# Send_Medicine_Motor.net
KiCad netlist of a schematic drawn in Altium Designer
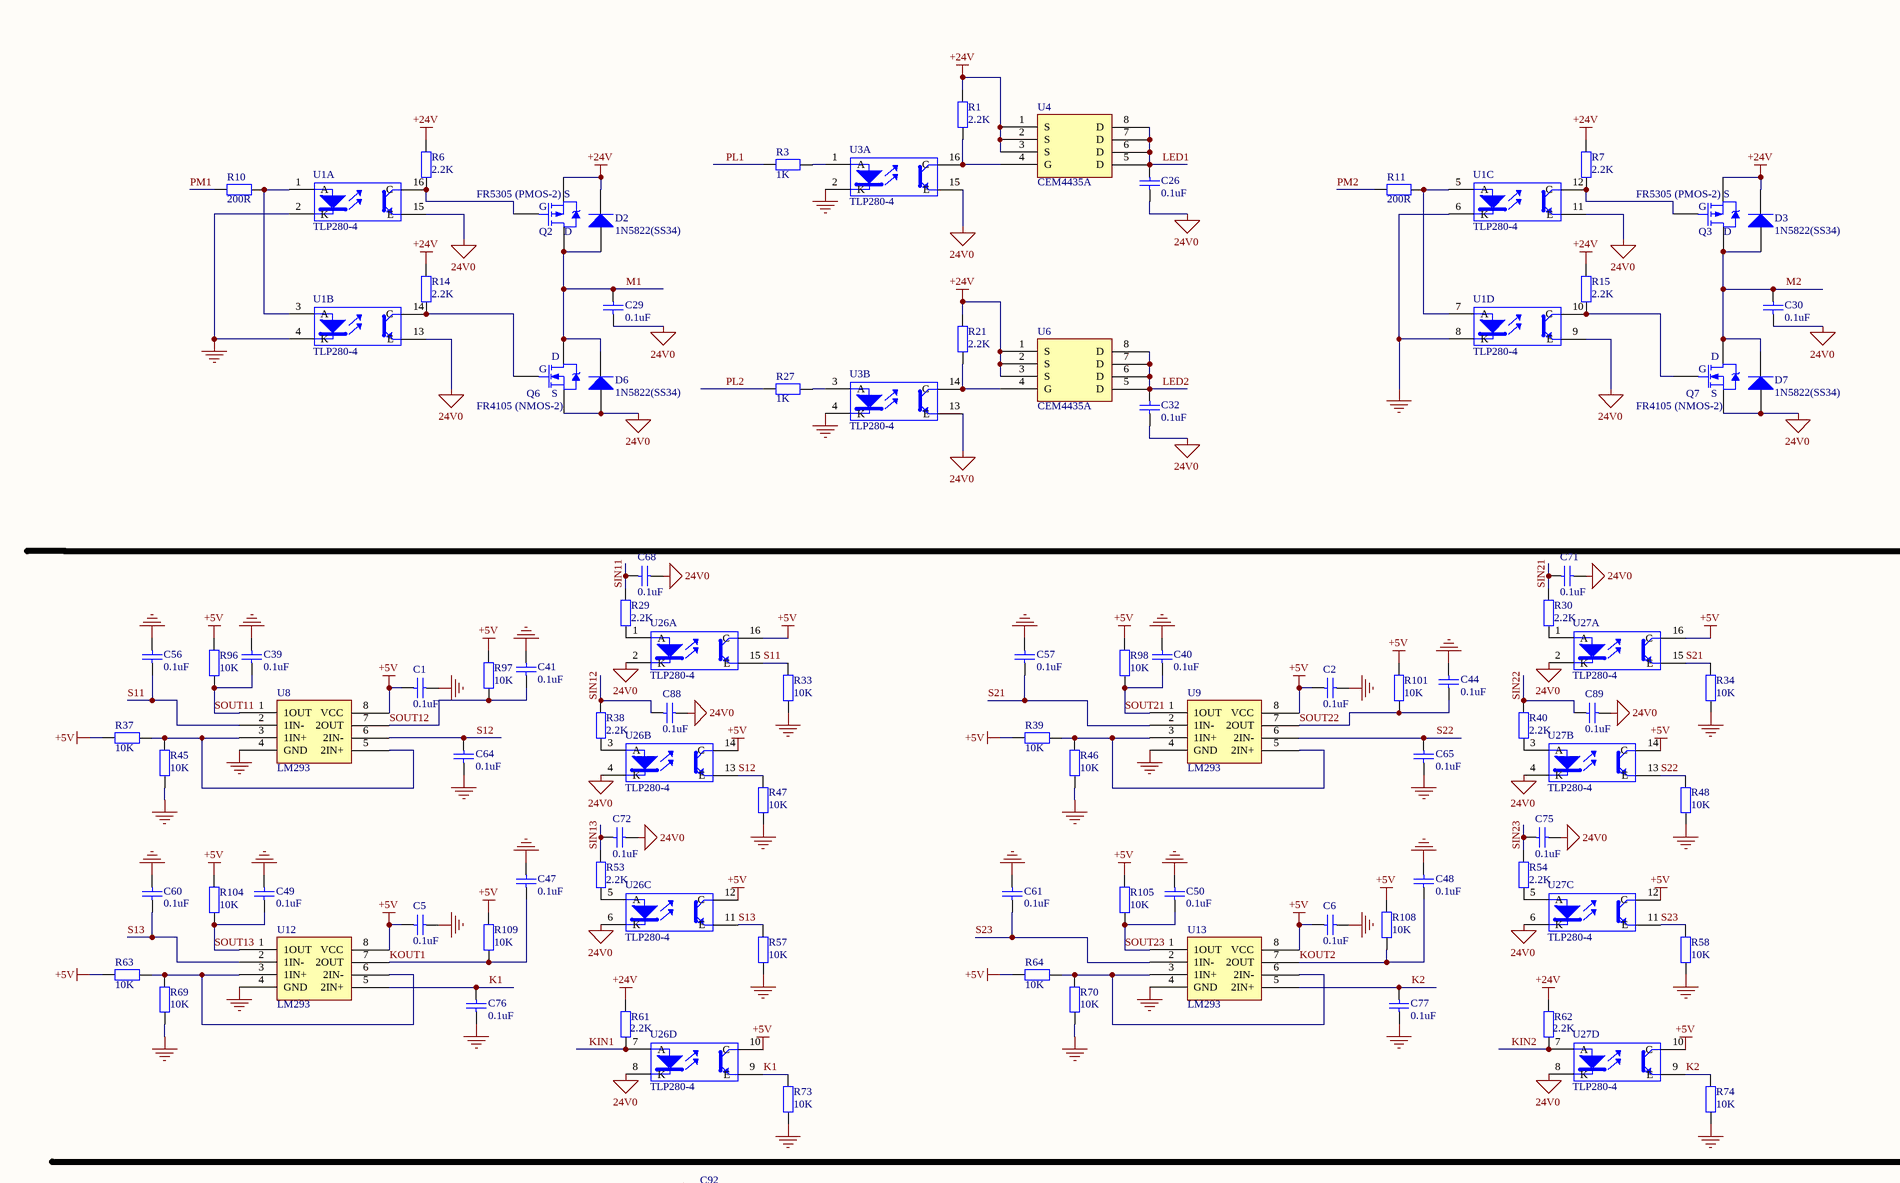
[diagram p0: Send_Medicine_Motor.SchDoc, top left]
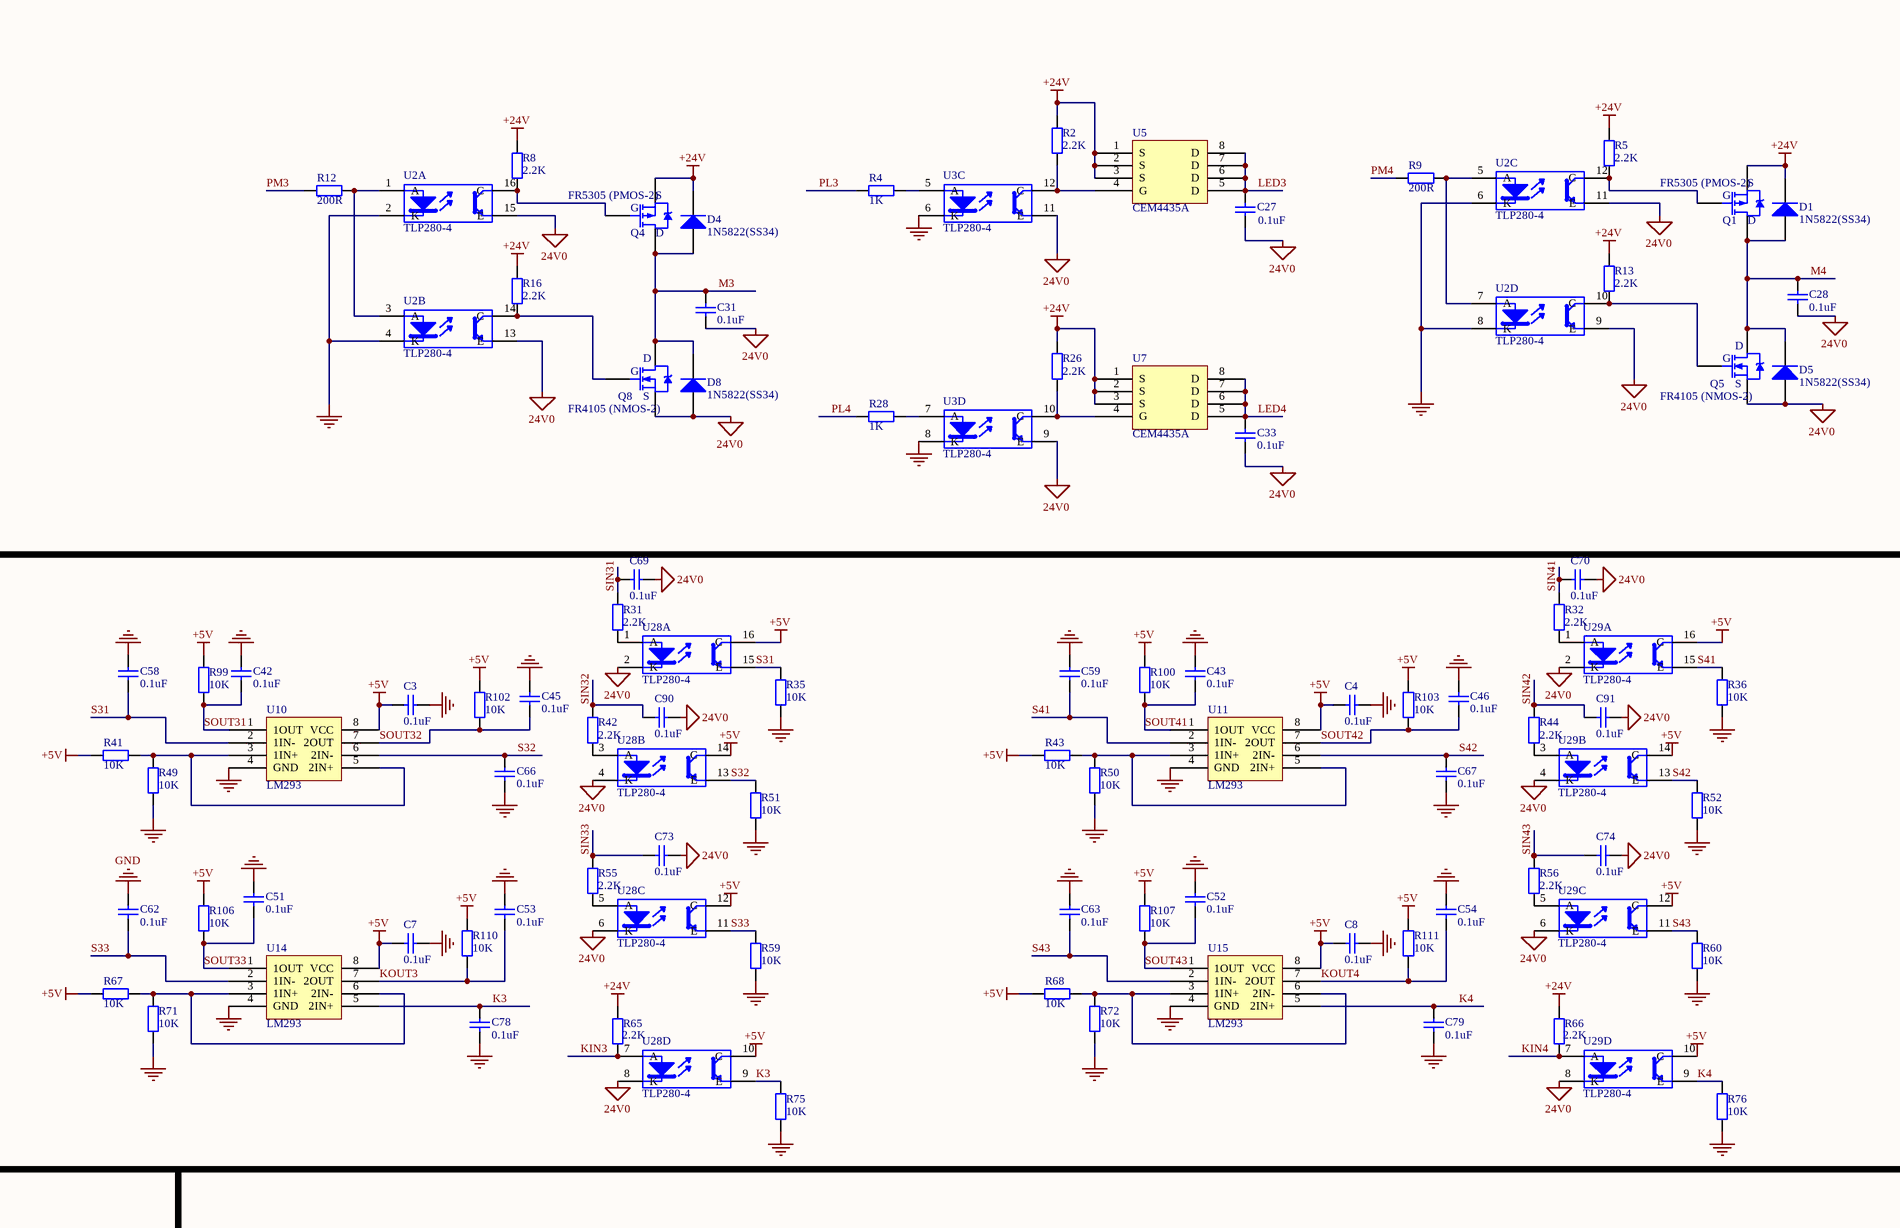
[diagram p1: Send_Medicine_Motor.SchDoc, top middle]
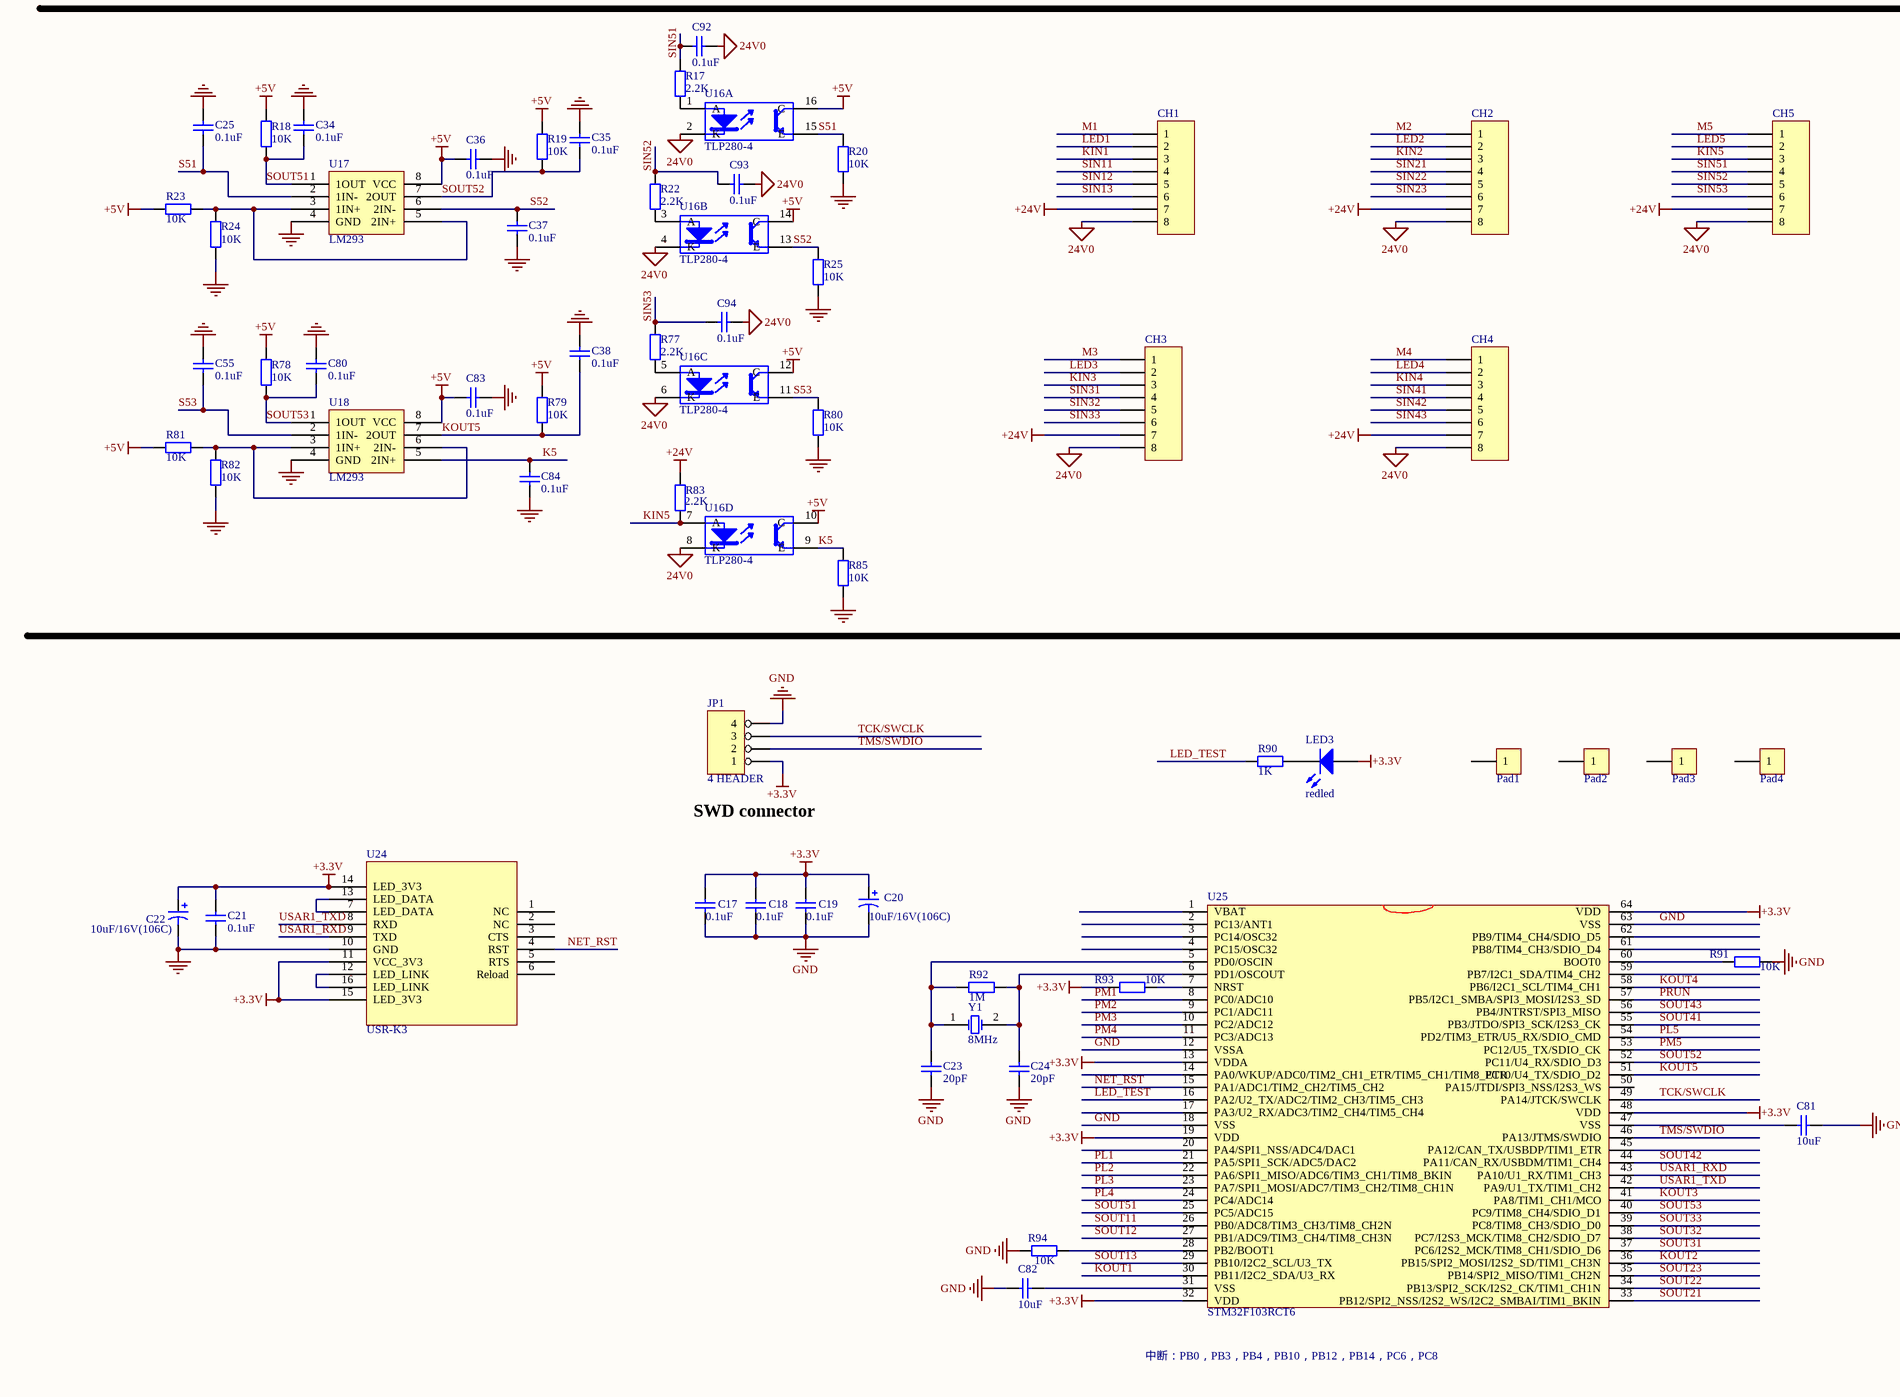
[diagram p2: Send_Medicine_Motor.SchDoc, bottom left]
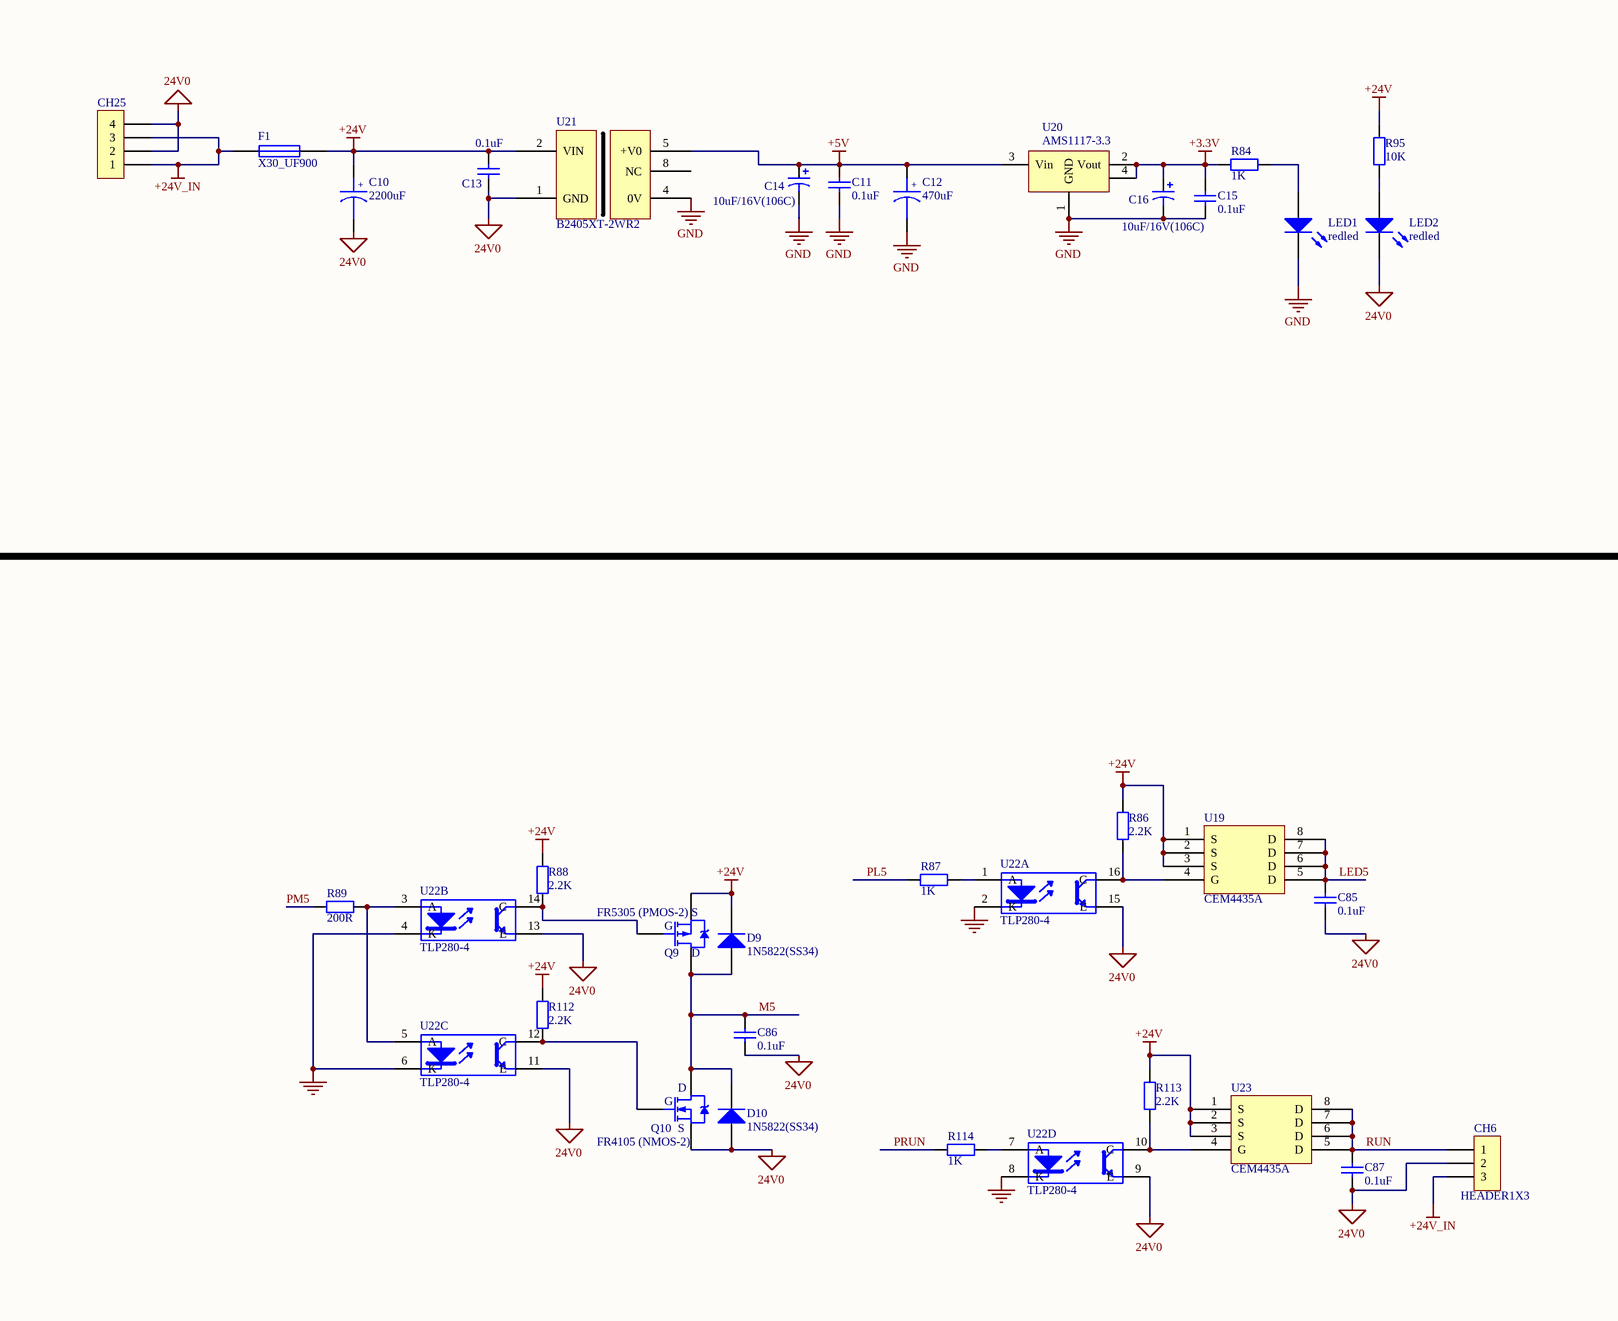
[diagram p3: Send_Medicine_Motor.SchDoc, bottom middle]

(export (version "E")
  (design (tool "Eeschema 10.0.6"))
  (components
    (comp (ref "C1")
      (value "0.1uF")
      (footprint "0805")
      (description "Capacitor")
      (fields (field (name "PUBLISHER") "Altium Limited"))
      (libsource (lib "Miscellaneous Devices") (part "Cap"))
    )
    (comp (ref "C2")
      (value "0.1uF")
      (footprint "0805")
      (description "Capacitor")
      (fields (field (name "PUBLISHER") "Altium Limited"))
      (libsource (lib "Miscellaneous Devices") (part "Cap"))
    )
    (comp (ref "C3")
      (value "0.1uF")
      (footprint "0805")
      (description "Capacitor")
      (fields (field (name "PUBLISHER") "Altium Limited"))
      (libsource (lib "Miscellaneous Devices") (part "Cap"))
    )
    (comp (ref "C4")
      (value "0.1uF")
      (footprint "0805")
      (description "Capacitor")
      (fields (field (name "PUBLISHER") "Altium Limited"))
      (libsource (lib "Miscellaneous Devices") (part "Cap"))
    )
    (comp (ref "C5")
      (value "0.1uF")
      (footprint "0805")
      (description "Capacitor")
      (fields (field (name "PUBLISHER") "Altium Limited"))
      (libsource (lib "Miscellaneous Devices") (part "Cap"))
    )
    (comp (ref "C6")
      (value "0.1uF")
      (footprint "0805")
      (description "Capacitor")
      (fields (field (name "PUBLISHER") "Altium Limited"))
      (libsource (lib "Miscellaneous Devices") (part "Cap"))
    )
    (comp (ref "C7")
      (value "0.1uF")
      (footprint "0805")
      (description "Capacitor")
      (fields (field (name "PUBLISHER") "Altium Limited"))
      (libsource (lib "Miscellaneous Devices") (part "Cap"))
    )
    (comp (ref "C8")
      (value "0.1uF")
      (footprint "0805")
      (description "Capacitor")
      (fields (field (name "PUBLISHER") "Altium Limited"))
      (libsource (lib "Miscellaneous Devices") (part "Cap"))
    )
    (comp (ref "C10")
      (value "2200uF")
      (footprint "C7.8*17")
      (fields (field (name "ALTIUM_UNNAMED_1") "2200uF"))
      (libsource (lib "myIntegrated_Library1") (part "C_2200uF"))
    )
    (comp (ref "C11")
      (value "0.1uF")
      (footprint "0805")
      (description "Capacitor")
      (fields (field (name "PUBLISHER") "Altium Limited"))
      (libsource (lib "Miscellaneous Devices") (part "Cap"))
    )
    (comp (ref "C12")
      (value "470uF")
      (footprint "C5*10")
      (fields (field (name "ALTIUM_UNNAMED_1") "470uF"))
      (libsource (lib "myIntegrated_Library1") (part "C_2200uF"))
    )
    (comp (ref "C13")
      (value "0.1uF")
      (footprint "0805")
      (description "Capacitor")
      (fields (field (name "PUBLISHER") "Altium Limited"))
      (libsource (lib "Miscellaneous Devices") (part "Cap"))
    )
    (comp (ref "C14")
      (value "10uF/16V(106C)")
      (footprint "CAP A-3216")
      (description "Polarized Capacitor (Surface Mount)")
      (fields (field (name "PUBLISHER") "Altium Limited"))
      (libsource (lib "Miscellaneous Devices") (part "Cap Pol3"))
    )
    (comp (ref "C15")
      (value "0.1uF")
      (footprint "0805")
      (description "Capacitor")
      (fields (field (name "PUBLISHER") "Altium Limited"))
      (libsource (lib "Miscellaneous Devices") (part "Cap"))
    )
    (comp (ref "C16")
      (value "10uF/16V(106C)")
      (footprint "CAP A-3216")
      (description "Polarized Capacitor (Surface Mount)")
      (fields (field (name "PUBLISHER") "Altium Limited"))
      (libsource (lib "Miscellaneous Devices") (part "Cap Pol3"))
    )
    (comp (ref "C17")
      (value "0.1uF")
      (footprint "0805")
      (description "Capacitor")
      (fields (field (name "PUBLISHER") "Altium Limited"))
      (libsource (lib "Miscellaneous Devices") (part "Cap"))
    )
    (comp (ref "C18")
      (value "0.1uF")
      (footprint "0805")
      (description "Capacitor")
      (fields (field (name "PUBLISHER") "Altium Limited"))
      (libsource (lib "Miscellaneous Devices") (part "Cap"))
    )
    (comp (ref "C19")
      (value "0.1uF")
      (footprint "0805")
      (description "Capacitor")
      (fields (field (name "PUBLISHER") "Altium Limited"))
      (libsource (lib "Miscellaneous Devices") (part "Cap"))
    )
    (comp (ref "C20")
      (value "10uF/16V(106C)")
      (footprint "CAP A-3216")
      (description "Polarized Capacitor (Surface Mount)")
      (fields (field (name "PUBLISHER") "Altium Limited"))
      (libsource (lib "Miscellaneous Devices") (part "Cap Pol3"))
    )
    (comp (ref "C21")
      (value "0.1uF")
      (footprint "0805")
      (description "Capacitor")
      (fields (field (name "PUBLISHER") "Altium Limited"))
      (libsource (lib "Miscellaneous Devices") (part "Cap"))
    )
    (comp (ref "C22")
      (value "10uF/16V(106C)")
      (footprint "CAP A-3216")
      (description "Polarized Capacitor (Surface Mount)")
      (fields (field (name "PUBLISHER") "Altium Limited"))
      (libsource (lib "Miscellaneous Devices") (part "Cap Pol3"))
    )
    (comp (ref "C23")
      (value "20pF")
      (footprint "0805")
      (description "Capacitor")
      (fields (field (name "PUBLISHER") "Altium Limited"))
      (libsource (lib "开发板元件库") (part "Cap"))
    )
    (comp (ref "C24")
      (value "20pF")
      (footprint "0805")
      (description "Capacitor")
      (fields (field (name "PUBLISHER") "Altium Limited"))
      (libsource (lib "开发板元件库") (part "Cap"))
    )
    (comp (ref "C25")
      (value "0.1uF")
      (footprint "0805")
      (description "Capacitor")
      (fields (field (name "PUBLISHER") "Altium Limited"))
      (libsource (lib "Miscellaneous Devices") (part "Cap"))
    )
    (comp (ref "C26")
      (value "0.1uF")
      (footprint "0805")
      (description "Capacitor")
      (fields (field (name "PUBLISHER") "Altium Limited"))
      (libsource (lib "Miscellaneous Devices") (part "Cap"))
    )
    (comp (ref "C27")
      (value "0.1uF")
      (footprint "0805")
      (description "Capacitor")
      (fields (field (name "PUBLISHER") "Altium Limited"))
      (libsource (lib "Miscellaneous Devices") (part "Cap"))
    )
    (comp (ref "C28")
      (value "0.1uF")
      (footprint "0805")
      (description "Capacitor")
      (fields (field (name "PUBLISHER") "Altium Limited"))
      (libsource (lib "Miscellaneous Devices") (part "Cap"))
    )
    (comp (ref "C29")
      (value "0.1uF")
      (footprint "0805")
      (description "Capacitor")
      (fields (field (name "PUBLISHER") "Altium Limited"))
      (libsource (lib "Miscellaneous Devices") (part "Cap"))
    )
    (comp (ref "C30")
      (value "0.1uF")
      (footprint "0805")
      (description "Capacitor")
      (fields (field (name "PUBLISHER") "Altium Limited"))
      (libsource (lib "Miscellaneous Devices") (part "Cap"))
    )
    (comp (ref "C31")
      (value "0.1uF")
      (footprint "0805")
      (description "Capacitor")
      (fields (field (name "PUBLISHER") "Altium Limited"))
      (libsource (lib "Miscellaneous Devices") (part "Cap"))
    )
    (comp (ref "C32")
      (value "0.1uF")
      (footprint "0805")
      (description "Capacitor")
      (fields (field (name "PUBLISHER") "Altium Limited"))
      (libsource (lib "Miscellaneous Devices") (part "Cap"))
    )
    (comp (ref "C33")
      (value "0.1uF")
      (footprint "0805")
      (description "Capacitor")
      (fields (field (name "PUBLISHER") "Altium Limited"))
      (libsource (lib "Miscellaneous Devices") (part "Cap"))
    )
    (comp (ref "C34")
      (value "0.1uF")
      (footprint "0805")
      (description "Capacitor")
      (fields (field (name "PUBLISHER") "Altium Limited"))
      (libsource (lib "Miscellaneous Devices") (part "Cap"))
    )
    (comp (ref "C35")
      (value "0.1uF")
      (footprint "0805")
      (description "Capacitor")
      (fields (field (name "PUBLISHER") "Altium Limited"))
      (libsource (lib "Miscellaneous Devices") (part "Cap"))
    )
    (comp (ref "C36")
      (value "0.1uF")
      (footprint "0805")
      (description "Capacitor")
      (fields (field (name "PUBLISHER") "Altium Limited"))
      (libsource (lib "Miscellaneous Devices") (part "Cap"))
    )
    (comp (ref "C37")
      (value "0.1uF")
      (footprint "0805")
      (description "Capacitor")
      (fields (field (name "PUBLISHER") "Altium Limited"))
      (libsource (lib "Miscellaneous Devices") (part "Cap"))
    )
    (comp (ref "C38")
      (value "0.1uF")
      (footprint "0805")
      (description "Capacitor")
      (fields (field (name "PUBLISHER") "Altium Limited"))
      (libsource (lib "Miscellaneous Devices") (part "Cap"))
    )
    (comp (ref "C39")
      (value "0.1uF")
      (footprint "0805")
      (description "Capacitor")
      (fields (field (name "PUBLISHER") "Altium Limited"))
      (libsource (lib "Miscellaneous Devices") (part "Cap"))
    )
    (comp (ref "C40")
      (value "0.1uF")
      (footprint "0805")
      (description "Capacitor")
      (fields (field (name "PUBLISHER") "Altium Limited"))
      (libsource (lib "Miscellaneous Devices") (part "Cap"))
    )
    (comp (ref "C41")
      (value "0.1uF")
      (footprint "0805")
      (description "Capacitor")
      (fields (field (name "PUBLISHER") "Altium Limited"))
      (libsource (lib "Miscellaneous Devices") (part "Cap"))
    )
    (comp (ref "C42")
      (value "0.1uF")
      (footprint "0805")
      (description "Capacitor")
      (fields (field (name "PUBLISHER") "Altium Limited"))
      (libsource (lib "Miscellaneous Devices") (part "Cap"))
    )
    (comp (ref "C43")
      (value "0.1uF")
      (footprint "0805")
      (description "Capacitor")
      (fields (field (name "PUBLISHER") "Altium Limited"))
      (libsource (lib "Miscellaneous Devices") (part "Cap"))
    )
    (comp (ref "C44")
      (value "0.1uF")
      (footprint "0805")
      (description "Capacitor")
      (fields (field (name "PUBLISHER") "Altium Limited"))
      (libsource (lib "Miscellaneous Devices") (part "Cap"))
    )
    (comp (ref "C45")
      (value "0.1uF")
      (footprint "0805")
      (description "Capacitor")
      (fields (field (name "PUBLISHER") "Altium Limited"))
      (libsource (lib "Miscellaneous Devices") (part "Cap"))
    )
    (comp (ref "C46")
      (value "0.1uF")
      (footprint "0805")
      (description "Capacitor")
      (fields (field (name "PUBLISHER") "Altium Limited"))
      (libsource (lib "Miscellaneous Devices") (part "Cap"))
    )
    (comp (ref "C47")
      (value "0.1uF")
      (footprint "0805")
      (description "Capacitor")
      (fields (field (name "PUBLISHER") "Altium Limited"))
      (libsource (lib "Miscellaneous Devices") (part "Cap"))
    )
    (comp (ref "C48")
      (value "0.1uF")
      (footprint "0805")
      (description "Capacitor")
      (fields (field (name "PUBLISHER") "Altium Limited"))
      (libsource (lib "Miscellaneous Devices") (part "Cap"))
    )
    (comp (ref "C49")
      (value "0.1uF")
      (footprint "0805")
      (description "Capacitor")
      (fields (field (name "PUBLISHER") "Altium Limited"))
      (libsource (lib "Miscellaneous Devices") (part "Cap"))
    )
    (comp (ref "C50")
      (value "0.1uF")
      (footprint "0805")
      (description "Capacitor")
      (fields (field (name "PUBLISHER") "Altium Limited"))
      (libsource (lib "Miscellaneous Devices") (part "Cap"))
    )
    (comp (ref "C51")
      (value "0.1uF")
      (footprint "0805")
      (description "Capacitor")
      (fields (field (name "PUBLISHER") "Altium Limited"))
      (libsource (lib "Miscellaneous Devices") (part "Cap"))
    )
    (comp (ref "C52")
      (value "0.1uF")
      (footprint "0805")
      (description "Capacitor")
      (fields (field (name "PUBLISHER") "Altium Limited"))
      (libsource (lib "Miscellaneous Devices") (part "Cap"))
    )
    (comp (ref "C53")
      (value "0.1uF")
      (footprint "0805")
      (description "Capacitor")
      (fields (field (name "PUBLISHER") "Altium Limited"))
      (libsource (lib "Miscellaneous Devices") (part "Cap"))
    )
    (comp (ref "C54")
      (value "0.1uF")
      (footprint "0805")
      (description "Capacitor")
      (fields (field (name "PUBLISHER") "Altium Limited"))
      (libsource (lib "Miscellaneous Devices") (part "Cap"))
    )
    (comp (ref "C55")
      (value "0.1uF")
      (footprint "0805")
      (description "Capacitor")
      (fields (field (name "PUBLISHER") "Altium Limited"))
      (libsource (lib "Miscellaneous Devices") (part "Cap"))
    )
    (comp (ref "C56")
      (value "0.1uF")
      (footprint "0805")
      (description "Capacitor")
      (fields (field (name "PUBLISHER") "Altium Limited"))
      (libsource (lib "Miscellaneous Devices") (part "Cap"))
    )
    (comp (ref "C57")
      (value "0.1uF")
      (footprint "0805")
      (description "Capacitor")
      (fields (field (name "PUBLISHER") "Altium Limited"))
      (libsource (lib "Miscellaneous Devices") (part "Cap"))
    )
    (comp (ref "C58")
      (value "0.1uF")
      (footprint "0805")
      (description "Capacitor")
      (fields (field (name "PUBLISHER") "Altium Limited"))
      (libsource (lib "Miscellaneous Devices") (part "Cap"))
    )
    (comp (ref "C59")
      (value "0.1uF")
      (footprint "0805")
      (description "Capacitor")
      (fields (field (name "PUBLISHER") "Altium Limited"))
      (libsource (lib "Miscellaneous Devices") (part "Cap"))
    )
    (comp (ref "C60")
      (value "0.1uF")
      (footprint "0805")
      (description "Capacitor")
      (fields (field (name "PUBLISHER") "Altium Limited"))
      (libsource (lib "Miscellaneous Devices") (part "Cap"))
    )
    (comp (ref "C61")
      (value "0.1uF")
      (footprint "0805")
      (description "Capacitor")
      (fields (field (name "PUBLISHER") "Altium Limited"))
      (libsource (lib "Miscellaneous Devices") (part "Cap"))
    )
    (comp (ref "C62")
      (value "0.1uF")
      (footprint "0805")
      (description "Capacitor")
      (fields (field (name "PUBLISHER") "Altium Limited"))
      (libsource (lib "Miscellaneous Devices") (part "Cap"))
    )
    (comp (ref "C63")
      (value "0.1uF")
      (footprint "0805")
      (description "Capacitor")
      (fields (field (name "PUBLISHER") "Altium Limited"))
      (libsource (lib "Miscellaneous Devices") (part "Cap"))
    )
    (comp (ref "C64")
      (value "0.1uF")
      (footprint "0805")
      (description "Capacitor")
      (fields (field (name "PUBLISHER") "Altium Limited"))
      (libsource (lib "Miscellaneous Devices") (part "Cap"))
    )
    (comp (ref "C65")
      (value "0.1uF")
      (footprint "0805")
      (description "Capacitor")
      (fields (field (name "PUBLISHER") "Altium Limited"))
      (libsource (lib "Miscellaneous Devices") (part "Cap"))
    )
    (comp (ref "C66")
      (value "0.1uF")
      (footprint "0805")
      (description "Capacitor")
      (fields (field (name "PUBLISHER") "Altium Limited"))
      (libsource (lib "Miscellaneous Devices") (part "Cap"))
    )
    (comp (ref "C67")
      (value "0.1uF")
      (footprint "0805")
      (description "Capacitor")
      (fields (field (name "PUBLISHER") "Altium Limited"))
      (libsource (lib "Miscellaneous Devices") (part "Cap"))
    )
    (comp (ref "C68")
      (value "0.1uF")
      (footprint "0805")
      (description "Capacitor")
      (fields (field (name "PUBLISHER") "Altium Limited"))
      (libsource (lib "Miscellaneous Devices") (part "Cap"))
    )
    (comp (ref "C69")
      (value "0.1uF")
      (footprint "0805")
      (description "Capacitor")
      (fields (field (name "PUBLISHER") "Altium Limited"))
      (libsource (lib "Miscellaneous Devices") (part "Cap"))
    )
    (comp (ref "C70")
      (value "0.1uF")
      (footprint "0805")
      (description "Capacitor")
      (fields (field (name "PUBLISHER") "Altium Limited"))
      (libsource (lib "Miscellaneous Devices") (part "Cap"))
    )
    (comp (ref "C71")
      (value "0.1uF")
      (footprint "0805")
      (description "Capacitor")
      (fields (field (name "PUBLISHER") "Altium Limited"))
      (libsource (lib "Miscellaneous Devices") (part "Cap"))
    )
    (comp (ref "C72")
      (value "0.1uF")
      (footprint "0805")
      (description "Capacitor")
      (fields (field (name "PUBLISHER") "Altium Limited"))
      (libsource (lib "Miscellaneous Devices") (part "Cap"))
    )
    (comp (ref "C73")
      (value "0.1uF")
      (footprint "0805")
      (description "Capacitor")
      (fields (field (name "PUBLISHER") "Altium Limited"))
      (libsource (lib "Miscellaneous Devices") (part "Cap"))
    )
    (comp (ref "C74")
      (value "0.1uF")
      (footprint "0805")
      (description "Capacitor")
      (fields (field (name "PUBLISHER") "Altium Limited"))
      (libsource (lib "Miscellaneous Devices") (part "Cap"))
    )
    (comp (ref "C75")
      (value "0.1uF")
      (footprint "0805")
      (description "Capacitor")
      (fields (field (name "PUBLISHER") "Altium Limited"))
      (libsource (lib "Miscellaneous Devices") (part "Cap"))
    )
    (comp (ref "C76")
      (value "0.1uF")
      (footprint "0805")
      (description "Capacitor")
      (fields (field (name "PUBLISHER") "Altium Limited"))
      (libsource (lib "Miscellaneous Devices") (part "Cap"))
    )
    (comp (ref "C77")
      (value "0.1uF")
      (footprint "0805")
      (description "Capacitor")
      (fields (field (name "PUBLISHER") "Altium Limited"))
      (libsource (lib "Miscellaneous Devices") (part "Cap"))
    )
    (comp (ref "C78")
      (value "0.1uF")
      (footprint "0805")
      (description "Capacitor")
      (fields (field (name "PUBLISHER") "Altium Limited"))
      (libsource (lib "Miscellaneous Devices") (part "Cap"))
    )
    (comp (ref "C79")
      (value "0.1uF")
      (footprint "0805")
      (description "Capacitor")
      (fields (field (name "PUBLISHER") "Altium Limited"))
      (libsource (lib "Miscellaneous Devices") (part "Cap"))
    )
    (comp (ref "C80")
      (value "0.1uF")
      (footprint "0805")
      (description "Capacitor")
      (fields (field (name "PUBLISHER") "Altium Limited"))
      (libsource (lib "Miscellaneous Devices") (part "Cap"))
    )
    (comp (ref "C81")
      (value "10uF")
      (footprint "0805")
      (description "Capacitor")
      (fields (field (name "PUBLISHER") "Altium Limited"))
      (libsource (lib "Miscellaneous Devices") (part "Cap"))
    )
    (comp (ref "C82")
      (value "10uF")
      (footprint "0805")
      (description "Capacitor")
      (fields (field (name "PUBLISHER") "Altium Limited"))
      (libsource (lib "Miscellaneous Devices") (part "Cap"))
    )
    (comp (ref "C83")
      (value "0.1uF")
      (footprint "0805")
      (description "Capacitor")
      (fields (field (name "PUBLISHER") "Altium Limited"))
      (libsource (lib "Miscellaneous Devices") (part "Cap"))
    )
    (comp (ref "C84")
      (value "0.1uF")
      (footprint "0805")
      (description "Capacitor")
      (fields (field (name "PUBLISHER") "Altium Limited"))
      (libsource (lib "Miscellaneous Devices") (part "Cap"))
    )
    (comp (ref "C85")
      (value "0.1uF")
      (footprint "0805")
      (description "Capacitor")
      (fields (field (name "PUBLISHER") "Altium Limited"))
      (libsource (lib "Miscellaneous Devices") (part "Cap"))
    )
    (comp (ref "C86")
      (value "0.1uF")
      (footprint "0805")
      (description "Capacitor")
      (fields (field (name "PUBLISHER") "Altium Limited"))
      (libsource (lib "Miscellaneous Devices") (part "Cap"))
    )
    (comp (ref "C87")
      (value "0.1uF")
      (footprint "0805")
      (description "Capacitor")
      (fields (field (name "PUBLISHER") "Altium Limited"))
      (libsource (lib "Miscellaneous Devices") (part "Cap"))
    )
    (comp (ref "C88")
      (value "0.1uF")
      (footprint "0805")
      (description "Capacitor")
      (fields (field (name "PUBLISHER") "Altium Limited"))
      (libsource (lib "Miscellaneous Devices") (part "Cap"))
    )
    (comp (ref "C89")
      (value "0.1uF")
      (footprint "0805")
      (description "Capacitor")
      (fields (field (name "PUBLISHER") "Altium Limited"))
      (libsource (lib "Miscellaneous Devices") (part "Cap"))
    )
    (comp (ref "C90")
      (value "0.1uF")
      (footprint "0805")
      (description "Capacitor")
      (fields (field (name "PUBLISHER") "Altium Limited"))
      (libsource (lib "Miscellaneous Devices") (part "Cap"))
    )
    (comp (ref "C91")
      (value "0.1uF")
      (footprint "0805")
      (description "Capacitor")
      (fields (field (name "PUBLISHER") "Altium Limited"))
      (libsource (lib "Miscellaneous Devices") (part "Cap"))
    )
    (comp (ref "C92")
      (value "0.1uF")
      (footprint "0805")
      (description "Capacitor")
      (fields (field (name "PUBLISHER") "Altium Limited"))
      (libsource (lib "Miscellaneous Devices") (part "Cap"))
    )
    (comp (ref "C93")
      (value "0.1uF")
      (footprint "0805")
      (description "Capacitor")
      (fields (field (name "PUBLISHER") "Altium Limited"))
      (libsource (lib "Miscellaneous Devices") (part "Cap"))
    )
    (comp (ref "C94")
      (value "0.1uF")
      (footprint "0805")
      (description "Capacitor")
      (fields (field (name "PUBLISHER") "Altium Limited"))
      (libsource (lib "Miscellaneous Devices") (part "Cap"))
    )
    (comp (ref "CH1")
      (value "HEADER1X8")
      (footprint "CH3.96-8PIN")
      (description "Header, 8-Pin")
      (libsource (lib "myIntegrated_Library1") (part "HEADER1X8"))
    )
    (comp (ref "CH2")
      (value "HEADER1X8")
      (footprint "CH3.96-8PIN")
      (description "Header, 8-Pin")
      (libsource (lib "myIntegrated_Library1") (part "HEADER1X8"))
    )
    (comp (ref "CH3")
      (value "HEADER1X8")
      (footprint "CH3.96-8PIN")
      (description "Header, 8-Pin")
      (libsource (lib "myIntegrated_Library1") (part "HEADER1X8"))
    )
    (comp (ref "CH4")
      (value "HEADER1X8")
      (footprint "CH3.96-8PIN")
      (description "Header, 8-Pin")
      (libsource (lib "myIntegrated_Library1") (part "HEADER1X8"))
    )
    (comp (ref "CH5")
      (value "HEADER1X8")
      (footprint "CH3.96-8PIN")
      (description "Header, 8-Pin")
      (libsource (lib "myIntegrated_Library1") (part "HEADER1X8"))
    )
    (comp (ref "CH6")
      (value "HEADER1X3")
      (footprint "CH3.96-3PIN")
      (libsource (lib "myIntegrated_Library1") (part "HEADER1X3"))
    )
    (comp (ref "CH25")
      (value "HEADER1X4")
      (footprint "CH3.96-4PIN")
      (libsource (lib "myIntegrated_Library1") (part "HEADER1X4"))
    )
    (comp (ref "D1")
      (value "1N5822(SS34)")
      (description "High Conductance Fast Diode")
      (fields (field (name "PUBLISHER") "Altium Limited"))
      (libsource (lib "Miscellaneous Devices") (part "Diode 1N4148"))
    )
    (comp (ref "D2")
      (value "1N5822(SS34)")
      (description "High Conductance Fast Diode")
      (fields (field (name "PUBLISHER") "Altium Limited"))
      (libsource (lib "Miscellaneous Devices") (part "Diode 1N4148"))
    )
    (comp (ref "D3")
      (value "1N5822(SS34)")
      (description "High Conductance Fast Diode")
      (fields (field (name "PUBLISHER") "Altium Limited"))
      (libsource (lib "Miscellaneous Devices") (part "Diode 1N4148"))
    )
    (comp (ref "D4")
      (value "1N5822(SS34)")
      (description "High Conductance Fast Diode")
      (fields (field (name "PUBLISHER") "Altium Limited"))
      (libsource (lib "Miscellaneous Devices") (part "Diode 1N4148"))
    )
    (comp (ref "D5")
      (value "1N5822(SS34)")
      (description "High Conductance Fast Diode")
      (fields (field (name "PUBLISHER") "Altium Limited"))
      (libsource (lib "Miscellaneous Devices") (part "Diode 1N4148"))
    )
    (comp (ref "D6")
      (value "1N5822(SS34)")
      (description "High Conductance Fast Diode")
      (fields (field (name "PUBLISHER") "Altium Limited"))
      (libsource (lib "Miscellaneous Devices") (part "Diode 1N4148"))
    )
    (comp (ref "D7")
      (value "1N5822(SS34)")
      (description "High Conductance Fast Diode")
      (fields (field (name "PUBLISHER") "Altium Limited"))
      (libsource (lib "Miscellaneous Devices") (part "Diode 1N4148"))
    )
    (comp (ref "D8")
      (value "1N5822(SS34)")
      (description "High Conductance Fast Diode")
      (fields (field (name "PUBLISHER") "Altium Limited"))
      (libsource (lib "Miscellaneous Devices") (part "Diode 1N4148"))
    )
    (comp (ref "D9")
      (value "1N5822(SS34)")
      (description "High Conductance Fast Diode")
      (fields (field (name "PUBLISHER") "Altium Limited"))
      (libsource (lib "Miscellaneous Devices") (part "Diode 1N4148"))
    )
    (comp (ref "D10")
      (value "1N5822(SS34)")
      (description "High Conductance Fast Diode")
      (fields (field (name "PUBLISHER") "Altium Limited"))
      (libsource (lib "Miscellaneous Devices") (part "Diode 1N4148"))
    )
    (comp (ref "F1")
      (value "X30_UF900")
      (footprint "X30UF900")
      (description "Fuse")
      (fields (field (name "PUBLISHER") "Altium Limited"))
      (libsource (lib "Miscellaneous Devices") (part "Fuse 1"))
    )
    (comp (ref "JP1")
      (value "4 HEADER")
      (footprint "CON4_1.5")
      (description "4 Pin Header")
      (libsource (lib "Miscellaneous Devices") (part "4 HEADER"))
    )
    (comp (ref "LED1")
      (value "redled")
      (footprint "LED-0805")
      (description "Typical RED, GREEN, YELLOW, AMBER GaAs LED")
      (fields (field (name "PUBLISHER") "Altium Limited"))
      (libsource (lib "Miscellaneous Devices") (part "LED2"))
    )
    (comp (ref "LED2")
      (value "redled")
      (footprint "LED-0805")
      (description "Typical RED, GREEN, YELLOW, AMBER GaAs LED")
      (fields (field (name "PUBLISHER") "Altium Limited"))
      (libsource (lib "Miscellaneous Devices") (part "LED2"))
    )
    (comp (ref "LED3")
      (value "redled")
      (footprint "LED-0805")
      (description "Typical RED, GREEN, YELLOW, AMBER GaAs LED")
      (fields (field (name "PUBLISHER") "Altium Limited"))
      (libsource (lib "Miscellaneous Devices") (part "LED2"))
    )
    (comp (ref "Pad1")
      (value "Pad")
      (footprint "pad35")
      (libsource (lib "myIntegrated_Library1") (part "Pad"))
    )
    (comp (ref "Pad2")
      (value "Pad")
      (footprint "pad35")
      (libsource (lib "myIntegrated_Library1") (part "Pad"))
    )
    (comp (ref "Pad3")
      (value "Pad")
      (footprint "pad35")
      (libsource (lib "myIntegrated_Library1") (part "Pad"))
    )
    (comp (ref "Pad4")
      (value "Pad")
      (footprint "pad35")
      (libsource (lib "myIntegrated_Library1") (part "Pad"))
    )
    (comp (ref "Q1")
      (value "FR5305 (PMOS-2)")
      (footprint "TO-252")
      (description "P-Channel Power MOSFET")
      (fields (field (name "PUBLISHER") "Altium Limited"))
      (libsource (lib "Miscellaneous Devices") (part "PMOS-2"))
    )
    (comp (ref "Q2")
      (value "FR5305 (PMOS-2)")
      (footprint "TO-252")
      (description "P-Channel Power MOSFET")
      (fields (field (name "PUBLISHER") "Altium Limited"))
      (libsource (lib "Miscellaneous Devices") (part "PMOS-2"))
    )
    (comp (ref "Q3")
      (value "FR5305 (PMOS-2)")
      (footprint "TO-252")
      (description "P-Channel Power MOSFET")
      (fields (field (name "PUBLISHER") "Altium Limited"))
      (libsource (lib "Miscellaneous Devices") (part "PMOS-2"))
    )
    (comp (ref "Q4")
      (value "FR5305 (PMOS-2)")
      (footprint "TO-252")
      (description "P-Channel Power MOSFET")
      (fields (field (name "PUBLISHER") "Altium Limited"))
      (libsource (lib "Miscellaneous Devices") (part "PMOS-2"))
    )
    (comp (ref "Q5")
      (value "FR4105 (NMOS-2)")
      (footprint "TO-252")
      (description "N-Channel Power MOSFET")
      (fields (field (name "PUBLISHER") "Altium Limited"))
      (libsource (lib "Miscellaneous Devices") (part "NMOS-2"))
    )
    (comp (ref "Q6")
      (value "FR4105 (NMOS-2)")
      (footprint "TO-252")
      (description "N-Channel Power MOSFET")
      (fields (field (name "PUBLISHER") "Altium Limited"))
      (libsource (lib "Miscellaneous Devices") (part "NMOS-2"))
    )
    (comp (ref "Q7")
      (value "FR4105 (NMOS-2)")
      (footprint "TO-252")
      (description "N-Channel Power MOSFET")
      (fields (field (name "PUBLISHER") "Altium Limited"))
      (libsource (lib "Miscellaneous Devices") (part "NMOS-2"))
    )
    (comp (ref "Q8")
      (value "FR4105 (NMOS-2)")
      (footprint "TO-252")
      (description "N-Channel Power MOSFET")
      (fields (field (name "PUBLISHER") "Altium Limited"))
      (libsource (lib "Miscellaneous Devices") (part "NMOS-2"))
    )
    (comp (ref "Q9")
      (value "FR5305 (PMOS-2)")
      (footprint "TO-252")
      (description "P-Channel Power MOSFET")
      (fields (field (name "PUBLISHER") "Altium Limited"))
      (libsource (lib "Miscellaneous Devices") (part "PMOS-2"))
    )
    (comp (ref "Q10")
      (value "FR4105 (NMOS-2)")
      (footprint "TO-252")
      (description "N-Channel Power MOSFET")
      (fields (field (name "PUBLISHER") "Altium Limited"))
      (libsource (lib "Miscellaneous Devices") (part "NMOS-2"))
    )
    (comp (ref "R1")
      (value "2.2K")
      (footprint "0805")
      (description "Resistor")
      (fields (field (name "PUBLISHER") "Altium Limited"))
      (libsource (lib "") (part "Res2_1"))
    )
    (comp (ref "R2")
      (value "2.2K")
      (footprint "0805")
      (description "Resistor")
      (fields (field (name "PUBLISHER") "Altium Limited"))
      (libsource (lib "") (part "Res2_1"))
    )
    (comp (ref "R3")
      (value "1K")
      (footprint "0805")
      (description "Resistor")
      (fields (field (name "PUBLISHER") "Altium Limited"))
      (libsource (lib "") (part "Res2_2"))
    )
    (comp (ref "R4")
      (value "1K")
      (footprint "0805")
      (description "Resistor")
      (fields (field (name "PUBLISHER") "Altium Limited"))
      (libsource (lib "") (part "Res2_2"))
    )
    (comp (ref "R5")
      (value "2.2K")
      (footprint "0805")
      (description "Resistor")
      (fields (field (name "PUBLISHER") "Altium Limited"))
      (libsource (lib "") (part "Res2_1"))
    )
    (comp (ref "R6")
      (value "2.2K")
      (footprint "0805")
      (description "Resistor")
      (fields (field (name "PUBLISHER") "Altium Limited"))
      (libsource (lib "") (part "Res2_1"))
    )
    (comp (ref "R7")
      (value "2.2K")
      (footprint "0805")
      (description "Resistor")
      (fields (field (name "PUBLISHER") "Altium Limited"))
      (libsource (lib "") (part "Res2_1"))
    )
    (comp (ref "R8")
      (value "2.2K")
      (footprint "0805")
      (description "Resistor")
      (fields (field (name "PUBLISHER") "Altium Limited"))
      (libsource (lib "") (part "Res2_1"))
    )
    (comp (ref "R9")
      (value "200R")
      (footprint "0805")
      (description "Resistor")
      (fields (field (name "PUBLISHER") "Altium Limited"))
      (libsource (lib "") (part "Res2_2"))
    )
    (comp (ref "R10")
      (value "200R")
      (footprint "0805")
      (description "Resistor")
      (fields (field (name "PUBLISHER") "Altium Limited"))
      (libsource (lib "") (part "Res2_2"))
    )
    (comp (ref "R11")
      (value "200R")
      (footprint "0805")
      (description "Resistor")
      (fields (field (name "PUBLISHER") "Altium Limited"))
      (libsource (lib "") (part "Res2_2"))
    )
    (comp (ref "R12")
      (value "200R")
      (footprint "0805")
      (description "Resistor")
      (fields (field (name "PUBLISHER") "Altium Limited"))
      (libsource (lib "") (part "Res2_2"))
    )
    (comp (ref "R13")
      (value "2.2K")
      (footprint "0805")
      (description "Resistor")
      (fields (field (name "PUBLISHER") "Altium Limited"))
      (libsource (lib "") (part "Res2_1"))
    )
    (comp (ref "R14")
      (value "2.2K")
      (footprint "0805")
      (description "Resistor")
      (fields (field (name "PUBLISHER") "Altium Limited"))
      (libsource (lib "") (part "Res2_1"))
    )
    (comp (ref "R15")
      (value "2.2K")
      (footprint "0805")
      (description "Resistor")
      (fields (field (name "PUBLISHER") "Altium Limited"))
      (libsource (lib "") (part "Res2_1"))
    )
    (comp (ref "R16")
      (value "2.2K")
      (footprint "0805")
      (description "Resistor")
      (fields (field (name "PUBLISHER") "Altium Limited"))
      (libsource (lib "") (part "Res2_1"))
    )
    (comp (ref "R17")
      (value "2.2K")
      (footprint "0805")
      (description "Resistor")
      (fields (field (name "PUBLISHER") "Altium Limited"))
      (libsource (lib "Miscellaneous Devices") (part "Res2"))
    )
    (comp (ref "R18")
      (value "10K")
      (footprint "0805")
      (description "Resistor")
      (fields (field (name "PUBLISHER") "Altium Limited"))
      (libsource (lib "Miscellaneous Devices") (part "Res2"))
    )
    (comp (ref "R19")
      (value "10K")
      (footprint "0805")
      (description "Resistor")
      (fields (field (name "PUBLISHER") "Altium Limited"))
      (libsource (lib "Miscellaneous Devices") (part "Res2"))
    )
    (comp (ref "R20")
      (value "10K")
      (footprint "0805")
      (description "Resistor")
      (fields (field (name "PUBLISHER") "Altium Limited"))
      (libsource (lib "Miscellaneous Devices") (part "Res2"))
    )
    (comp (ref "R21")
      (value "2.2K")
      (footprint "0805")
      (description "Resistor")
      (fields (field (name "PUBLISHER") "Altium Limited"))
      (libsource (lib "") (part "Res2_1"))
    )
    (comp (ref "R22")
      (value "2.2K")
      (footprint "0805")
      (description "Resistor")
      (fields (field (name "PUBLISHER") "Altium Limited"))
      (libsource (lib "Miscellaneous Devices") (part "Res2"))
    )
    (comp (ref "R23")
      (value "10K")
      (footprint "0805")
      (description "Resistor")
      (fields (field (name "PUBLISHER") "Altium Limited"))
      (libsource (lib "") (part "Res2_2"))
    )
    (comp (ref "R24")
      (value "10K")
      (footprint "0805")
      (description "Resistor")
      (fields (field (name "PUBLISHER") "Altium Limited"))
      (libsource (lib "Miscellaneous Devices") (part "Res2"))
    )
    (comp (ref "R25")
      (value "10K")
      (footprint "0805")
      (description "Resistor")
      (fields (field (name "PUBLISHER") "Altium Limited"))
      (libsource (lib "Miscellaneous Devices") (part "Res2"))
    )
    (comp (ref "R26")
      (value "2.2K")
      (footprint "0805")
      (description "Resistor")
      (fields (field (name "PUBLISHER") "Altium Limited"))
      (libsource (lib "") (part "Res2_1"))
    )
    (comp (ref "R27")
      (value "1K")
      (footprint "0805")
      (description "Resistor")
      (fields (field (name "PUBLISHER") "Altium Limited"))
      (libsource (lib "") (part "Res2_2"))
    )
    (comp (ref "R28")
      (value "1K")
      (footprint "0805")
      (description "Resistor")
      (fields (field (name "PUBLISHER") "Altium Limited"))
      (libsource (lib "") (part "Res2_2"))
    )
    (comp (ref "R29")
      (value "2.2K")
      (footprint "0805")
      (description "Resistor")
      (fields (field (name "PUBLISHER") "Altium Limited"))
      (libsource (lib "Miscellaneous Devices") (part "Res2"))
    )
    (comp (ref "R30")
      (value "2.2K")
      (footprint "0805")
      (description "Resistor")
      (fields (field (name "PUBLISHER") "Altium Limited"))
      (libsource (lib "Miscellaneous Devices") (part "Res2"))
    )
    (comp (ref "R31")
      (value "2.2K")
      (footprint "0805")
      (description "Resistor")
      (fields (field (name "PUBLISHER") "Altium Limited"))
      (libsource (lib "Miscellaneous Devices") (part "Res2"))
    )
    (comp (ref "R32")
      (value "2.2K")
      (footprint "0805")
      (description "Resistor")
      (fields (field (name "PUBLISHER") "Altium Limited"))
      (libsource (lib "Miscellaneous Devices") (part "Res2"))
    )
    (comp (ref "R33")
      (value "10K")
      (footprint "0805")
      (description "Resistor")
      (fields (field (name "PUBLISHER") "Altium Limited"))
      (libsource (lib "Miscellaneous Devices") (part "Res2"))
    )
    (comp (ref "R34")
      (value "10K")
      (footprint "0805")
      (description "Resistor")
      (fields (field (name "PUBLISHER") "Altium Limited"))
      (libsource (lib "Miscellaneous Devices") (part "Res2"))
    )
    (comp (ref "R35")
      (value "10K")
      (footprint "0805")
      (description "Resistor")
      (fields (field (name "PUBLISHER") "Altium Limited"))
      (libsource (lib "Miscellaneous Devices") (part "Res2"))
    )
    (comp (ref "R36")
      (value "10K")
      (footprint "0805")
      (description "Resistor")
      (fields (field (name "PUBLISHER") "Altium Limited"))
      (libsource (lib "Miscellaneous Devices") (part "Res2"))
    )
    (comp (ref "R37")
      (value "10K")
      (footprint "0805")
      (description "Resistor")
      (fields (field (name "PUBLISHER") "Altium Limited"))
      (libsource (lib "") (part "Res2_2"))
    )
    (comp (ref "R38")
      (value "2.2K")
      (footprint "0805")
      (description "Resistor")
      (fields (field (name "PUBLISHER") "Altium Limited"))
      (libsource (lib "Miscellaneous Devices") (part "Res2"))
    )
    (comp (ref "R39")
      (value "10K")
      (footprint "0805")
      (description "Resistor")
      (fields (field (name "PUBLISHER") "Altium Limited"))
      (libsource (lib "") (part "Res2_2"))
    )
    (comp (ref "R40")
      (value "2.2K")
      (footprint "0805")
      (description "Resistor")
      (fields (field (name "PUBLISHER") "Altium Limited"))
      (libsource (lib "Miscellaneous Devices") (part "Res2"))
    )
    (comp (ref "R41")
      (value "10K")
      (footprint "0805")
      (description "Resistor")
      (fields (field (name "PUBLISHER") "Altium Limited"))
      (libsource (lib "") (part "Res2_2"))
    )
    (comp (ref "R42")
      (value "2.2K")
      (footprint "0805")
      (description "Resistor")
      (fields (field (name "PUBLISHER") "Altium Limited"))
      (libsource (lib "Miscellaneous Devices") (part "Res2"))
    )
    (comp (ref "R43")
      (value "10K")
      (footprint "0805")
      (description "Resistor")
      (fields (field (name "PUBLISHER") "Altium Limited"))
      (libsource (lib "") (part "Res2_2"))
    )
    (comp (ref "R44")
      (value "2.2K")
      (footprint "0805")
      (description "Resistor")
      (fields (field (name "PUBLISHER") "Altium Limited"))
      (libsource (lib "Miscellaneous Devices") (part "Res2"))
    )
    (comp (ref "R45")
      (value "10K")
      (footprint "0805")
      (description "Resistor")
      (fields (field (name "PUBLISHER") "Altium Limited"))
      (libsource (lib "Miscellaneous Devices") (part "Res2"))
    )
    (comp (ref "R46")
      (value "10K")
      (footprint "0805")
      (description "Resistor")
      (fields (field (name "PUBLISHER") "Altium Limited"))
      (libsource (lib "Miscellaneous Devices") (part "Res2"))
    )
    (comp (ref "R47")
      (value "10K")
      (footprint "0805")
      (description "Resistor")
      (fields (field (name "PUBLISHER") "Altium Limited"))
      (libsource (lib "Miscellaneous Devices") (part "Res2"))
    )
    (comp (ref "R48")
      (value "10K")
      (footprint "0805")
      (description "Resistor")
      (fields (field (name "PUBLISHER") "Altium Limited"))
      (libsource (lib "Miscellaneous Devices") (part "Res2"))
    )
    (comp (ref "R49")
      (value "10K")
      (footprint "0805")
      (description "Resistor")
      (fields (field (name "PUBLISHER") "Altium Limited"))
      (libsource (lib "Miscellaneous Devices") (part "Res2"))
    )
    (comp (ref "R50")
      (value "10K")
      (footprint "0805")
      (description "Resistor")
      (fields (field (name "PUBLISHER") "Altium Limited"))
      (libsource (lib "Miscellaneous Devices") (part "Res2"))
    )
    (comp (ref "R51")
      (value "10K")
      (footprint "0805")
      (description "Resistor")
      (fields (field (name "PUBLISHER") "Altium Limited"))
      (libsource (lib "Miscellaneous Devices") (part "Res2"))
    )
    (comp (ref "R52")
      (value "10K")
      (footprint "0805")
      (description "Resistor")
      (fields (field (name "PUBLISHER") "Altium Limited"))
      (libsource (lib "Miscellaneous Devices") (part "Res2"))
    )
    (comp (ref "R53")
      (value "2.2K")
      (footprint "0805")
      (description "Resistor")
      (fields (field (name "PUBLISHER") "Altium Limited"))
      (libsource (lib "Miscellaneous Devices") (part "Res2"))
    )
    (comp (ref "R54")
      (value "2.2K")
      (footprint "0805")
      (description "Resistor")
      (fields (field (name "PUBLISHER") "Altium Limited"))
      (libsource (lib "Miscellaneous Devices") (part "Res2"))
    )
    (comp (ref "R55")
      (value "2.2K")
      (footprint "0805")
      (description "Resistor")
      (fields (field (name "PUBLISHER") "Altium Limited"))
      (libsource (lib "Miscellaneous Devices") (part "Res2"))
    )
    (comp (ref "R56")
      (value "2.2K")
      (footprint "0805")
      (description "Resistor")
      (fields (field (name "PUBLISHER") "Altium Limited"))
      (libsource (lib "Miscellaneous Devices") (part "Res2"))
    )
    (comp (ref "R57")
      (value "10K")
      (footprint "0805")
      (description "Resistor")
      (fields (field (name "PUBLISHER") "Altium Limited"))
      (libsource (lib "Miscellaneous Devices") (part "Res2"))
    )
    (comp (ref "R58")
      (value "10K")
      (footprint "0805")
      (description "Resistor")
      (fields (field (name "PUBLISHER") "Altium Limited"))
      (libsource (lib "Miscellaneous Devices") (part "Res2"))
    )
    (comp (ref "R59")
      (value "10K")
      (footprint "0805")
      (description "Resistor")
      (fields (field (name "PUBLISHER") "Altium Limited"))
      (libsource (lib "Miscellaneous Devices") (part "Res2"))
    )
    (comp (ref "R60")
      (value "10K")
      (footprint "0805")
      (description "Resistor")
      (fields (field (name "PUBLISHER") "Altium Limited"))
      (libsource (lib "Miscellaneous Devices") (part "Res2"))
    )
    (comp (ref "R61")
      (value "2.2K")
      (footprint "0805")
      (description "Resistor")
      (fields (field (name "PUBLISHER") "Altium Limited"))
      (libsource (lib "Miscellaneous Devices") (part "Res2"))
    )
    (comp (ref "R62")
      (value "2.2K")
      (footprint "0805")
      (description "Resistor")
      (fields (field (name "PUBLISHER") "Altium Limited"))
      (libsource (lib "Miscellaneous Devices") (part "Res2"))
    )
    (comp (ref "R63")
      (value "10K")
      (footprint "0805")
      (description "Resistor")
      (fields (field (name "PUBLISHER") "Altium Limited"))
      (libsource (lib "") (part "Res2_2"))
    )
    (comp (ref "R64")
      (value "10K")
      (footprint "0805")
      (description "Resistor")
      (fields (field (name "PUBLISHER") "Altium Limited"))
      (libsource (lib "") (part "Res2_2"))
    )
    (comp (ref "R65")
      (value "2.2K")
      (footprint "0805")
      (description "Resistor")
      (fields (field (name "PUBLISHER") "Altium Limited"))
      (libsource (lib "Miscellaneous Devices") (part "Res2"))
    )
    (comp (ref "R66")
      (value "2.2K")
      (footprint "0805")
      (description "Resistor")
      (fields (field (name "PUBLISHER") "Altium Limited"))
      (libsource (lib "Miscellaneous Devices") (part "Res2"))
    )
    (comp (ref "R67")
      (value "10K")
      (footprint "0805")
      (description "Resistor")
      (fields (field (name "PUBLISHER") "Altium Limited"))
      (libsource (lib "") (part "Res2_2"))
    )
    (comp (ref "R68")
      (value "10K")
      (footprint "0805")
      (description "Resistor")
      (fields (field (name "PUBLISHER") "Altium Limited"))
      (libsource (lib "") (part "Res2_2"))
    )
    (comp (ref "R69")
      (value "10K")
      (footprint "0805")
      (description "Resistor")
      (fields (field (name "PUBLISHER") "Altium Limited"))
      (libsource (lib "Miscellaneous Devices") (part "Res2"))
    )
    (comp (ref "R70")
      (value "10K")
      (footprint "0805")
      (description "Resistor")
      (fields (field (name "PUBLISHER") "Altium Limited"))
      (libsource (lib "Miscellaneous Devices") (part "Res2"))
    )
    (comp (ref "R71")
      (value "10K")
      (footprint "0805")
      (description "Resistor")
      (fields (field (name "PUBLISHER") "Altium Limited"))
      (libsource (lib "Miscellaneous Devices") (part "Res2"))
    )
    (comp (ref "R72")
      (value "10K")
      (footprint "0805")
      (description "Resistor")
      (fields (field (name "PUBLISHER") "Altium Limited"))
      (libsource (lib "Miscellaneous Devices") (part "Res2"))
    )
    (comp (ref "R73")
      (value "10K")
      (footprint "0805")
      (description "Resistor")
      (fields (field (name "PUBLISHER") "Altium Limited"))
      (libsource (lib "Miscellaneous Devices") (part "Res2"))
    )
    (comp (ref "R74")
      (value "10K")
      (footprint "0805")
      (description "Resistor")
      (fields (field (name "PUBLISHER") "Altium Limited"))
      (libsource (lib "Miscellaneous Devices") (part "Res2"))
    )
    (comp (ref "R75")
      (value "10K")
      (footprint "0805")
      (description "Resistor")
      (fields (field (name "PUBLISHER") "Altium Limited"))
      (libsource (lib "Miscellaneous Devices") (part "Res2"))
    )
    (comp (ref "R76")
      (value "10K")
      (footprint "0805")
      (description "Resistor")
      (fields (field (name "PUBLISHER") "Altium Limited"))
      (libsource (lib "Miscellaneous Devices") (part "Res2"))
    )
    (comp (ref "R77")
      (value "2.2K")
      (footprint "0805")
      (description "Resistor")
      (fields (field (name "PUBLISHER") "Altium Limited"))
      (libsource (lib "Miscellaneous Devices") (part "Res2"))
    )
    (comp (ref "R78")
      (value "10K")
      (footprint "0805")
      (description "Resistor")
      (fields (field (name "PUBLISHER") "Altium Limited"))
      (libsource (lib "Miscellaneous Devices") (part "Res2"))
    )
    (comp (ref "R79")
      (value "10K")
      (footprint "0805")
      (description "Resistor")
      (fields (field (name "PUBLISHER") "Altium Limited"))
      (libsource (lib "Miscellaneous Devices") (part "Res2"))
    )
    (comp (ref "R80")
      (value "10K")
      (footprint "0805")
      (description "Resistor")
      (fields (field (name "PUBLISHER") "Altium Limited"))
      (libsource (lib "Miscellaneous Devices") (part "Res2"))
    )
    (comp (ref "R81")
      (value "10K")
      (footprint "0805")
      (description "Resistor")
      (fields (field (name "PUBLISHER") "Altium Limited"))
      (libsource (lib "") (part "Res2_2"))
    )
    (comp (ref "R82")
      (value "10K")
      (footprint "0805")
      (description "Resistor")
      (fields (field (name "PUBLISHER") "Altium Limited"))
      (libsource (lib "Miscellaneous Devices") (part "Res2"))
    )
    (comp (ref "R83")
      (value "2.2K")
      (footprint "0805")
      (description "Resistor")
      (fields (field (name "PUBLISHER") "Altium Limited"))
      (libsource (lib "Miscellaneous Devices") (part "Res2"))
    )
    (comp (ref "R84")
      (value "1K")
      (footprint "0805")
      (description "Resistor")
      (fields (field (name "PUBLISHER") "Altium Limited"))
      (libsource (lib "") (part "Res2_3"))
    )
    (comp (ref "R85")
      (value "10K")
      (footprint "0805")
      (description "Resistor")
      (fields (field (name "PUBLISHER") "Altium Limited"))
      (libsource (lib "Miscellaneous Devices") (part "Res2"))
    )
    (comp (ref "R86")
      (value "2.2K")
      (footprint "0805")
      (description "Resistor")
      (fields (field (name "PUBLISHER") "Altium Limited"))
      (libsource (lib "") (part "Res2_1"))
    )
    (comp (ref "R87")
      (value "1K")
      (footprint "0805")
      (description "Resistor")
      (fields (field (name "PUBLISHER") "Altium Limited"))
      (libsource (lib "") (part "Res2_2"))
    )
    (comp (ref "R88")
      (value "2.2K")
      (footprint "0805")
      (description "Resistor")
      (fields (field (name "PUBLISHER") "Altium Limited"))
      (libsource (lib "") (part "Res2_1"))
    )
    (comp (ref "R89")
      (value "200R")
      (footprint "0805")
      (description "Resistor")
      (fields (field (name "PUBLISHER") "Altium Limited"))
      (libsource (lib "") (part "Res2_2"))
    )
    (comp (ref "R90")
      (value "1K")
      (footprint "0805")
      (description "Resistor")
      (fields (field (name "PUBLISHER") "Altium Limited"))
      (libsource (lib "") (part "Res2_2"))
    )
    (comp (ref "R91")
      (value "10K")
      (footprint "0805")
      (description "Resistor")
      (fields (field (name "PUBLISHER") "Altium Limited"))
      (libsource (lib "") (part "Res2_1"))
    )
    (comp (ref "R92")
      (value "1M")
      (footprint "0805")
      (description "Resistor")
      (fields (field (name "PUBLISHER") "Altium Limited"))
      (libsource (lib "开发板元件库") (part "Res2"))
    )
    (comp (ref "R93")
      (value "10K")
      (footprint "0805")
      (description "Resistor")
      (fields (field (name "PUBLISHER") "Altium Limited"))
      (libsource (lib "开发板元件库") (part "Res2"))
    )
    (comp (ref "R94")
      (value "10K")
      (footprint "0805")
      (description "Resistor")
      (fields (field (name "PUBLISHER") "Altium Limited"))
      (libsource (lib "开发板元件库") (part "Res2"))
    )
    (comp (ref "R95")
      (value "10K")
      (footprint "0805")
      (description "Resistor")
      (fields (field (name "PUBLISHER") "Altium Limited"))
      (libsource (lib "") (part "Res2_1"))
    )
    (comp (ref "R96")
      (value "10K")
      (footprint "0805")
      (description "Resistor")
      (fields (field (name "PUBLISHER") "Altium Limited"))
      (libsource (lib "Miscellaneous Devices") (part "Res2"))
    )
    (comp (ref "R97")
      (value "10K")
      (footprint "0805")
      (description "Resistor")
      (fields (field (name "PUBLISHER") "Altium Limited"))
      (libsource (lib "Miscellaneous Devices") (part "Res2"))
    )
    (comp (ref "R98")
      (value "10K")
      (footprint "0805")
      (description "Resistor")
      (fields (field (name "PUBLISHER") "Altium Limited"))
      (libsource (lib "Miscellaneous Devices") (part "Res2"))
    )
    (comp (ref "R99")
      (value "10K")
      (footprint "0805")
      (description "Resistor")
      (fields (field (name "PUBLISHER") "Altium Limited"))
      (libsource (lib "Miscellaneous Devices") (part "Res2"))
    )
    (comp (ref "R100")
      (value "10K")
      (footprint "0805")
      (description "Resistor")
      (fields (field (name "PUBLISHER") "Altium Limited"))
      (libsource (lib "Miscellaneous Devices") (part "Res2"))
    )
    (comp (ref "R101")
      (value "10K")
      (footprint "0805")
      (description "Resistor")
      (fields (field (name "PUBLISHER") "Altium Limited"))
      (libsource (lib "Miscellaneous Devices") (part "Res2"))
    )
    (comp (ref "R102")
      (value "10K")
      (footprint "0805")
      (description "Resistor")
      (fields (field (name "PUBLISHER") "Altium Limited"))
      (libsource (lib "Miscellaneous Devices") (part "Res2"))
    )
    (comp (ref "R103")
      (value "10K")
      (footprint "0805")
      (description "Resistor")
      (fields (field (name "PUBLISHER") "Altium Limited"))
      (libsource (lib "Miscellaneous Devices") (part "Res2"))
    )
    (comp (ref "R104")
      (value "10K")
      (footprint "0805")
      (description "Resistor")
      (fields (field (name "PUBLISHER") "Altium Limited"))
      (libsource (lib "Miscellaneous Devices") (part "Res2"))
    )
    (comp (ref "R105")
      (value "10K")
      (footprint "0805")
      (description "Resistor")
      (fields (field (name "PUBLISHER") "Altium Limited"))
      (libsource (lib "Miscellaneous Devices") (part "Res2"))
    )
    (comp (ref "R106")
      (value "10K")
      (footprint "0805")
      (description "Resistor")
      (fields (field (name "PUBLISHER") "Altium Limited"))
      (libsource (lib "Miscellaneous Devices") (part "Res2"))
    )
    (comp (ref "R107")
      (value "10K")
      (footprint "0805")
      (description "Resistor")
      (fields (field (name "PUBLISHER") "Altium Limited"))
      (libsource (lib "Miscellaneous Devices") (part "Res2"))
    )
    (comp (ref "R108")
      (value "10K")
      (footprint "0805")
      (description "Resistor")
      (fields (field (name "PUBLISHER") "Altium Limited"))
      (libsource (lib "Miscellaneous Devices") (part "Res2"))
    )
    (comp (ref "R109")
      (value "10K")
      (footprint "0805")
      (description "Resistor")
      (fields (field (name "PUBLISHER") "Altium Limited"))
      (libsource (lib "Miscellaneous Devices") (part "Res2"))
    )
    (comp (ref "R110")
      (value "10K")
      (footprint "0805")
      (description "Resistor")
      (fields (field (name "PUBLISHER") "Altium Limited"))
      (libsource (lib "Miscellaneous Devices") (part "Res2"))
    )
    (comp (ref "R111")
      (value "10K")
      (footprint "0805")
      (description "Resistor")
      (fields (field (name "PUBLISHER") "Altium Limited"))
      (libsource (lib "Miscellaneous Devices") (part "Res2"))
    )
    (comp (ref "R112")
      (value "2.2K")
      (footprint "0805")
      (description "Resistor")
      (fields (field (name "PUBLISHER") "Altium Limited"))
      (libsource (lib "") (part "Res2_1"))
    )
    (comp (ref "R113")
      (value "2.2K")
      (footprint "0805")
      (description "Resistor")
      (fields (field (name "PUBLISHER") "Altium Limited"))
      (libsource (lib "") (part "Res2_1"))
    )
    (comp (ref "R114")
      (value "1K")
      (footprint "0805")
      (description "Resistor")
      (fields (field (name "PUBLISHER") "Altium Limited"))
      (libsource (lib "") (part "Res2_2"))
    )
    (comp (ref "U1") (value "TLP280-4") (footprint "SO16") (libsource (lib "WH V20") (part "TLP521-4")))
    (comp (ref "U2") (value "TLP280-4") (footprint "SO16") (libsource (lib "WH V20") (part "TLP521-4")))
    (comp (ref "U3") (value "TLP280-4") (footprint "SO16") (libsource (lib "WH V20") (part "TLP521-4")))
    (comp (ref "U4")
      (value "CEM4435A")
      (footprint "SOP8-OP27")
      (libsource (lib "myIntegrated_Library1") (part "CEM4435A"))
    )
    (comp (ref "U5")
      (value "CEM4435A")
      (footprint "SOP8-OP27")
      (libsource (lib "myIntegrated_Library1") (part "CEM4435A"))
    )
    (comp (ref "U6")
      (value "CEM4435A")
      (footprint "SOP8-OP27")
      (libsource (lib "myIntegrated_Library1") (part "CEM4435A"))
    )
    (comp (ref "U7")
      (value "CEM4435A")
      (footprint "SOP8-OP27")
      (libsource (lib "myIntegrated_Library1") (part "CEM4435A"))
    )
    (comp (ref "U8")
      (value "LM293")
      (footprint "SOP8-OP27")
      (libsource (lib "myIntegrated_Library1") (part "LM293"))
    )
    (comp (ref "U9")
      (value "LM293")
      (footprint "SOP8-OP27")
      (libsource (lib "myIntegrated_Library1") (part "LM293"))
    )
    (comp (ref "U10")
      (value "LM293")
      (footprint "SOP8-OP27")
      (libsource (lib "myIntegrated_Library1") (part "LM293"))
    )
    (comp (ref "U11")
      (value "LM293")
      (footprint "SOP8-OP27")
      (libsource (lib "myIntegrated_Library1") (part "LM293"))
    )
    (comp (ref "U12")
      (value "LM293")
      (footprint "SOP8-OP27")
      (libsource (lib "myIntegrated_Library1") (part "LM293"))
    )
    (comp (ref "U13")
      (value "LM293")
      (footprint "SOP8-OP27")
      (libsource (lib "myIntegrated_Library1") (part "LM293"))
    )
    (comp (ref "U14")
      (value "LM293")
      (footprint "SOP8-OP27")
      (libsource (lib "myIntegrated_Library1") (part "LM293"))
    )
    (comp (ref "U15")
      (value "LM293")
      (footprint "SOP8-OP27")
      (libsource (lib "myIntegrated_Library1") (part "LM293"))
    )
    (comp (ref "U16") (value "TLP280-4") (footprint "SO16") (libsource (lib "WH V20") (part "TLP521-4")))
    (comp (ref "U17")
      (value "LM293")
      (footprint "SOP8-OP27")
      (libsource (lib "myIntegrated_Library1") (part "LM293"))
    )
    (comp (ref "U18")
      (value "LM293")
      (footprint "SOP8-OP27")
      (libsource (lib "myIntegrated_Library1") (part "LM293"))
    )
    (comp (ref "U19")
      (value "CEM4435A")
      (footprint "SOP8-OP27")
      (libsource (lib "myIntegrated_Library1") (part "CEM4435A"))
    )
    (comp (ref "U20")
      (value "AMS1117-3.3")
      (footprint "SOT223")
      (libsource (lib "货架电子标签元件库") (part "AMS1117-5"))
    )
    (comp (ref "U21")
      (value "B2405XT-2WR2")
      (footprint "B2405XT-2WR2")
      (libsource (lib "myIntegrated_Library1") (part "B2405XT-2WR2"))
    )
    (comp (ref "U22") (value "TLP280-4") (footprint "SO16") (libsource (lib "WH V20") (part "TLP521-4")))
    (comp (ref "U23")
      (value "CEM4435A")
      (footprint "SOP8-OP27")
      (libsource (lib "myIntegrated_Library1") (part "CEM4435A"))
    )
    (comp (ref "U24")
      (value "USR-K3")
      (footprint "USR-K3")
      (libsource (lib "myIntegrated_Library1") (part "USR-K3"))
    )
    (comp (ref "U25")
      (value "STM32F103RCT6")
      (footprint "stm32:LQFP64")
      (libsource (lib "stm32") (part "STM32F103RDT6"))
    )
    (comp (ref "U26") (value "TLP280-4") (footprint "SO16") (libsource (lib "WH V20") (part "TLP521-4")))
    (comp (ref "U27") (value "TLP280-4") (footprint "SO16") (libsource (lib "WH V20") (part "TLP521-4")))
    (comp (ref "U28") (value "TLP280-4") (footprint "SO16") (libsource (lib "WH V20") (part "TLP521-4")))
    (comp (ref "U29") (value "TLP280-4") (footprint "SO16") (libsource (lib "WH V20") (part "TLP521-4")))
    (comp (ref "Y1")
      (value "8MHz")
      (footprint "XTAL_US")
      (description "Crystal Oscillator")
      (fields (field (name "PUBLISHER") "Altium Limited"))
      (libsource (lib "战舰STM32开发板底板封装库") (part "XTAL"))
    )
  )
  (nets
    (net (code "1") (name "+3.3V") (class "Default")
      (node (ref "C15") (pin "2") (pinfunction "2_2") (pintype "passive"))
      (node (ref "C16") (pin "1") (pinfunction "1_1") (pintype "passive"))
      (node (ref "C17") (pin "2") (pinfunction "2_2") (pintype "passive"))
      (node (ref "C18") (pin "2") (pinfunction "2_2") (pintype "passive"))
      (node (ref "C19") (pin "2") (pinfunction "2_2") (pintype "passive"))
      (node (ref "C20") (pin "1") (pinfunction "1_1") (pintype "passive"))
      (node (ref "C21") (pin "2") (pinfunction "2_2") (pintype "passive"))
      (node (ref "C22") (pin "1") (pinfunction "1_1") (pintype "passive"))
      (node (ref "JP1") (pin "1") (pinfunction "1_1") (pintype "passive"))
      (node (ref "LED3") (pin "1") (pinfunction "A_1") (pintype "passive"))
      (node (ref "R84") (pin "2") (pinfunction "2_2") (pintype "passive"))
      (node (ref "R93") (pin "1") (pinfunction "1_1") (pintype "passive"))
      (node (ref "U20") (pin "2") (pinfunction "Vout_2") (pintype "passive"))
      (node (ref "U20") (pin "4") (pintype "passive"))
      (node (ref "U24") (pin "11") (pinfunction "VCC_3V3_11") (pintype "passive"))
      (node (ref "U24") (pin "14") (pinfunction "LED_3V3_14") (pintype "passive"))
      (node (ref "U24") (pin "15") (pinfunction "LED_3V3_15") (pintype "passive"))
      (node (ref "U25") (pin "13") (pinfunction "VDDA_13") (pintype "passive"))
      (node (ref "U25") (pin "19") (pinfunction "VDD_19") (pintype "passive"))
      (node (ref "U25") (pin "32") (pinfunction "VDD_32") (pintype "passive"))
      (node (ref "U25") (pin "48") (pinfunction "VDD_48") (pintype "passive"))
      (node (ref "U25") (pin "64") (pinfunction "VDD_64") (pintype "passive"))
    )
    (net (code "2") (name "+5V") (class "Default")
      (node (ref "C1") (pin "2") (pinfunction "2_2") (pintype "passive"))
      (node (ref "C11") (pin "2") (pinfunction "2_2") (pintype "passive"))
      (node (ref "C12") (pin "1") (pinfunction "1_1") (pintype "passive"))
      (node (ref "C14") (pin "1") (pinfunction "1_1") (pintype "passive"))
      (node (ref "C2") (pin "2") (pinfunction "2_2") (pintype "passive"))
      (node (ref "C3") (pin "2") (pinfunction "2_2") (pintype "passive"))
      (node (ref "C36") (pin "2") (pinfunction "2_2") (pintype "passive"))
      (node (ref "C4") (pin "2") (pinfunction "2_2") (pintype "passive"))
      (node (ref "C5") (pin "2") (pinfunction "2_2") (pintype "passive"))
      (node (ref "C6") (pin "2") (pinfunction "2_2") (pintype "passive"))
      (node (ref "C7") (pin "2") (pinfunction "2_2") (pintype "passive"))
      (node (ref "C8") (pin "2") (pinfunction "2_2") (pintype "passive"))
      (node (ref "C83") (pin "2") (pinfunction "2_2") (pintype "passive"))
      (node (ref "R100") (pin "1") (pinfunction "1_1") (pintype "passive"))
      (node (ref "R101") (pin "1") (pinfunction "1_1") (pintype "passive"))
      (node (ref "R102") (pin "1") (pinfunction "1_1") (pintype "passive"))
      (node (ref "R103") (pin "1") (pinfunction "1_1") (pintype "passive"))
      (node (ref "R104") (pin "1") (pinfunction "1_1") (pintype "passive"))
      (node (ref "R105") (pin "1") (pinfunction "1_1") (pintype "passive"))
      (node (ref "R106") (pin "1") (pinfunction "1_1") (pintype "passive"))
      (node (ref "R107") (pin "1") (pinfunction "1_1") (pintype "passive"))
      (node (ref "R108") (pin "1") (pinfunction "1_1") (pintype "passive"))
      (node (ref "R109") (pin "1") (pinfunction "1_1") (pintype "passive"))
      (node (ref "R110") (pin "1") (pinfunction "1_1") (pintype "passive"))
      (node (ref "R111") (pin "1") (pinfunction "1_1") (pintype "passive"))
      (node (ref "R18") (pin "1") (pinfunction "1_1") (pintype "passive"))
      (node (ref "R19") (pin "1") (pinfunction "1_1") (pintype "passive"))
      (node (ref "R23") (pin "1") (pinfunction "1_1") (pintype "passive"))
      (node (ref "R37") (pin "1") (pinfunction "1_1") (pintype "passive"))
      (node (ref "R39") (pin "1") (pinfunction "1_1") (pintype "passive"))
      (node (ref "R41") (pin "1") (pinfunction "1_1") (pintype "passive"))
      (node (ref "R43") (pin "1") (pinfunction "1_1") (pintype "passive"))
      (node (ref "R63") (pin "1") (pinfunction "1_1") (pintype "passive"))
      (node (ref "R64") (pin "1") (pinfunction "1_1") (pintype "passive"))
      (node (ref "R67") (pin "1") (pinfunction "1_1") (pintype "passive"))
      (node (ref "R68") (pin "1") (pinfunction "1_1") (pintype "passive"))
      (node (ref "R78") (pin "1") (pinfunction "1_1") (pintype "passive"))
      (node (ref "R79") (pin "1") (pinfunction "1_1") (pintype "passive"))
      (node (ref "R81") (pin "1") (pinfunction "1_1") (pintype "passive"))
      (node (ref "R96") (pin "1") (pinfunction "1_1") (pintype "passive"))
      (node (ref "R97") (pin "1") (pinfunction "1_1") (pintype "passive"))
      (node (ref "R98") (pin "1") (pinfunction "1_1") (pintype "passive"))
      (node (ref "R99") (pin "1") (pinfunction "1_1") (pintype "passive"))
      (node (ref "U10") (pin "8") (pinfunction "VCC_8") (pintype "passive"))
      (node (ref "U11") (pin "8") (pinfunction "VCC_8") (pintype "passive"))
      (node (ref "U12") (pin "8") (pinfunction "VCC_8") (pintype "passive"))
      (node (ref "U13") (pin "8") (pinfunction "VCC_8") (pintype "passive"))
      (node (ref "U14") (pin "8") (pinfunction "VCC_8") (pintype "passive"))
      (node (ref "U15") (pin "8") (pinfunction "VCC_8") (pintype "passive"))
      (node (ref "U16") (pin "10") (pinfunction "C_10") (pintype "passive"))
      (node (ref "U16") (pin "12") (pinfunction "C_12") (pintype "passive"))
      (node (ref "U16") (pin "14") (pinfunction "C_14") (pintype "passive"))
      (node (ref "U16") (pin "16") (pinfunction "C_16") (pintype "passive"))
      (node (ref "U17") (pin "8") (pinfunction "VCC_8") (pintype "passive"))
      (node (ref "U18") (pin "8") (pinfunction "VCC_8") (pintype "passive"))
      (node (ref "U20") (pin "3") (pinfunction "Vin_3") (pintype "passive"))
      (node (ref "U21") (pin "5") (pinfunction "+V0_5") (pintype "passive"))
      (node (ref "U26") (pin "10") (pinfunction "C_10") (pintype "passive"))
      (node (ref "U26") (pin "12") (pinfunction "C_12") (pintype "passive"))
      (node (ref "U26") (pin "14") (pinfunction "C_14") (pintype "passive"))
      (node (ref "U26") (pin "16") (pinfunction "C_16") (pintype "passive"))
      (node (ref "U27") (pin "10") (pinfunction "C_10") (pintype "passive"))
      (node (ref "U27") (pin "12") (pinfunction "C_12") (pintype "passive"))
      (node (ref "U27") (pin "14") (pinfunction "C_14") (pintype "passive"))
      (node (ref "U27") (pin "16") (pinfunction "C_16") (pintype "passive"))
      (node (ref "U28") (pin "10") (pinfunction "C_10") (pintype "passive"))
      (node (ref "U28") (pin "12") (pinfunction "C_12") (pintype "passive"))
      (node (ref "U28") (pin "14") (pinfunction "C_14") (pintype "passive"))
      (node (ref "U28") (pin "16") (pinfunction "C_16") (pintype "passive"))
      (node (ref "U29") (pin "10") (pinfunction "C_10") (pintype "passive"))
      (node (ref "U29") (pin "12") (pinfunction "C_12") (pintype "passive"))
      (node (ref "U29") (pin "14") (pinfunction "C_14") (pintype "passive"))
      (node (ref "U29") (pin "16") (pinfunction "C_16") (pintype "passive"))
      (node (ref "U8") (pin "8") (pinfunction "VCC_8") (pintype "passive"))
      (node (ref "U9") (pin "8") (pinfunction "VCC_8") (pintype "passive"))
    )
    (net (code "3") (name "+24V") (class "Default")
      (node (ref "C10") (pin "1") (pinfunction "1_1") (pintype "passive"))
      (node (ref "C13") (pin "2") (pinfunction "2_2") (pintype "passive"))
      (node (ref "CH1") (pin "7") (pinfunction "7_7") (pintype "passive"))
      (node (ref "CH2") (pin "7") (pinfunction "7_7") (pintype "passive"))
      (node (ref "CH3") (pin "7") (pinfunction "7_7") (pintype "passive"))
      (node (ref "CH4") (pin "7") (pinfunction "7_7") (pintype "passive"))
      (node (ref "CH5") (pin "7") (pinfunction "7_7") (pintype "passive"))
      (node (ref "D1") (pin "2") (pinfunction "K_2") (pintype "passive"))
      (node (ref "D2") (pin "2") (pinfunction "K_2") (pintype "passive"))
      (node (ref "D3") (pin "2") (pinfunction "K_2") (pintype "passive"))
      (node (ref "D4") (pin "2") (pinfunction "K_2") (pintype "passive"))
      (node (ref "D9") (pin "2") (pinfunction "K_2") (pintype "passive"))
      (node (ref "F1") (pin "2") (pinfunction "2_2") (pintype "passive"))
      (node (ref "Q1") (pin "3") (pinfunction "S_3") (pintype "passive"))
      (node (ref "Q2") (pin "3") (pinfunction "S_3") (pintype "passive"))
      (node (ref "Q3") (pin "3") (pinfunction "S_3") (pintype "passive"))
      (node (ref "Q4") (pin "3") (pinfunction "S_3") (pintype "passive"))
      (node (ref "Q9") (pin "3") (pinfunction "S_3") (pintype "passive"))
      (node (ref "R1") (pin "2") (pinfunction "2_2") (pintype "passive"))
      (node (ref "R112") (pin "2") (pinfunction "2_2") (pintype "passive"))
      (node (ref "R113") (pin "2") (pinfunction "2_2") (pintype "passive"))
      (node (ref "R13") (pin "2") (pinfunction "2_2") (pintype "passive"))
      (node (ref "R14") (pin "2") (pinfunction "2_2") (pintype "passive"))
      (node (ref "R15") (pin "2") (pinfunction "2_2") (pintype "passive"))
      (node (ref "R16") (pin "2") (pinfunction "2_2") (pintype "passive"))
      (node (ref "R2") (pin "2") (pinfunction "2_2") (pintype "passive"))
      (node (ref "R21") (pin "2") (pinfunction "2_2") (pintype "passive"))
      (node (ref "R26") (pin "2") (pinfunction "2_2") (pintype "passive"))
      (node (ref "R5") (pin "2") (pinfunction "2_2") (pintype "passive"))
      (node (ref "R6") (pin "2") (pinfunction "2_2") (pintype "passive"))
      (node (ref "R61") (pin "1") (pinfunction "1_1") (pintype "passive"))
      (node (ref "R62") (pin "1") (pinfunction "1_1") (pintype "passive"))
      (node (ref "R65") (pin "1") (pinfunction "1_1") (pintype "passive"))
      (node (ref "R66") (pin "1") (pinfunction "1_1") (pintype "passive"))
      (node (ref "R7") (pin "2") (pinfunction "2_2") (pintype "passive"))
      (node (ref "R8") (pin "2") (pinfunction "2_2") (pintype "passive"))
      (node (ref "R83") (pin "1") (pinfunction "1_1") (pintype "passive"))
      (node (ref "R86") (pin "2") (pinfunction "2_2") (pintype "passive"))
      (node (ref "R88") (pin "2") (pinfunction "2_2") (pintype "passive"))
      (node (ref "R95") (pin "2") (pinfunction "2_2") (pintype "passive"))
      (node (ref "U19") (pin "1") (pinfunction "S_1") (pintype "passive"))
      (node (ref "U19") (pin "2") (pinfunction "S_2") (pintype "passive"))
      (node (ref "U19") (pin "3") (pinfunction "S_3") (pintype "passive"))
      (node (ref "U21") (pin "2") (pinfunction "VIN_2") (pintype "passive"))
      (node (ref "U23") (pin "1") (pinfunction "S_1") (pintype "passive"))
      (node (ref "U23") (pin "2") (pinfunction "S_2") (pintype "passive"))
      (node (ref "U23") (pin "3") (pinfunction "S_3") (pintype "passive"))
      (node (ref "U4") (pin "1") (pinfunction "S_1") (pintype "passive"))
      (node (ref "U4") (pin "2") (pinfunction "S_2") (pintype "passive"))
      (node (ref "U4") (pin "3") (pinfunction "S_3") (pintype "passive"))
      (node (ref "U5") (pin "1") (pinfunction "S_1") (pintype "passive"))
      (node (ref "U5") (pin "2") (pinfunction "S_2") (pintype "passive"))
      (node (ref "U5") (pin "3") (pinfunction "S_3") (pintype "passive"))
      (node (ref "U6") (pin "1") (pinfunction "S_1") (pintype "passive"))
      (node (ref "U6") (pin "2") (pinfunction "S_2") (pintype "passive"))
      (node (ref "U6") (pin "3") (pinfunction "S_3") (pintype "passive"))
      (node (ref "U7") (pin "1") (pinfunction "S_1") (pintype "passive"))
      (node (ref "U7") (pin "2") (pinfunction "S_2") (pintype "passive"))
      (node (ref "U7") (pin "3") (pinfunction "S_3") (pintype "passive"))
    )
    (net (code "4") (name "+24V_IN") (class "Default")
      (node (ref "CH25") (pin "1") (pinfunction "1_1") (pintype "passive"))
      (node (ref "CH25") (pin "3") (pinfunction "3_3") (pintype "passive"))
      (node (ref "CH6") (pin "3") (pinfunction "3_3") (pintype "passive"))
      (node (ref "F1") (pin "1") (pinfunction "1_1") (pintype "passive"))
    )
    (net (code "5") (name "/K1") (class "Default")
      (node (ref "C76") (pin "2") (pinfunction "2_2") (pintype "passive"))
      (node (ref "R73") (pin "1") (pinfunction "1_1") (pintype "passive"))
      (node (ref "U12") (pin "5") (pinfunction "2IN+_5") (pintype "passive"))
      (node (ref "U26") (pin "9") (pinfunction "E_9") (pintype "passive"))
    )
    (net (code "6") (name "/K2") (class "Default")
      (node (ref "C77") (pin "2") (pinfunction "2_2") (pintype "passive"))
      (node (ref "R74") (pin "1") (pinfunction "1_1") (pintype "passive"))
      (node (ref "U13") (pin "5") (pinfunction "2IN+_5") (pintype "passive"))
      (node (ref "U27") (pin "9") (pinfunction "E_9") (pintype "passive"))
    )
    (net (code "7") (name "/K3") (class "Default")
      (node (ref "C78") (pin "2") (pinfunction "2_2") (pintype "passive"))
      (node (ref "R75") (pin "1") (pinfunction "1_1") (pintype "passive"))
      (node (ref "U14") (pin "5") (pinfunction "2IN+_5") (pintype "passive"))
      (node (ref "U28") (pin "9") (pinfunction "E_9") (pintype "passive"))
    )
    (net (code "8") (name "/K4") (class "Default")
      (node (ref "C79") (pin "2") (pinfunction "2_2") (pintype "passive"))
      (node (ref "R76") (pin "1") (pinfunction "1_1") (pintype "passive"))
      (node (ref "U15") (pin "5") (pinfunction "2IN+_5") (pintype "passive"))
      (node (ref "U29") (pin "9") (pinfunction "E_9") (pintype "passive"))
    )
    (net (code "9") (name "/K5") (class "Default")
      (node (ref "C84") (pin "2") (pinfunction "2_2") (pintype "passive"))
      (node (ref "R85") (pin "1") (pinfunction "1_1") (pintype "passive"))
      (node (ref "U16") (pin "9") (pinfunction "E_9") (pintype "passive"))
      (node (ref "U18") (pin "5") (pinfunction "2IN+_5") (pintype "passive"))
    )
    (net (code "10") (name "/KIN1") (class "Default")
      (node (ref "CH1") (pin "3") (pinfunction "3_3") (pintype "passive"))
      (node (ref "R61") (pin "2") (pinfunction "2_2") (pintype "passive"))
      (node (ref "U26") (pin "7") (pinfunction "A_7") (pintype "passive"))
    )
    (net (code "11") (name "/KIN2") (class "Default")
      (node (ref "CH2") (pin "3") (pinfunction "3_3") (pintype "passive"))
      (node (ref "R62") (pin "2") (pinfunction "2_2") (pintype "passive"))
      (node (ref "U27") (pin "7") (pinfunction "A_7") (pintype "passive"))
    )
    (net (code "12") (name "/KIN3") (class "Default")
      (node (ref "CH3") (pin "3") (pinfunction "3_3") (pintype "passive"))
      (node (ref "R65") (pin "2") (pinfunction "2_2") (pintype "passive"))
      (node (ref "U28") (pin "7") (pinfunction "A_7") (pintype "passive"))
    )
    (net (code "13") (name "/KIN4") (class "Default")
      (node (ref "CH4") (pin "3") (pinfunction "3_3") (pintype "passive"))
      (node (ref "R66") (pin "2") (pinfunction "2_2") (pintype "passive"))
      (node (ref "U29") (pin "7") (pinfunction "A_7") (pintype "passive"))
    )
    (net (code "14") (name "/KIN5") (class "Default")
      (node (ref "CH5") (pin "3") (pinfunction "3_3") (pintype "passive"))
      (node (ref "R83") (pin "2") (pinfunction "2_2") (pintype "passive"))
      (node (ref "U16") (pin "7") (pinfunction "A_7") (pintype "passive"))
    )
    (net (code "15") (name "/KOUT1") (class "Default")
      (node (ref "C47") (pin "2") (pinfunction "2_2") (pintype "passive"))
      (node (ref "R109") (pin "2") (pinfunction "2_2") (pintype "passive"))
      (node (ref "U12") (pin "7") (pinfunction "2OUT_7") (pintype "passive"))
      (node (ref "U25") (pin "30") (pinfunction "PB11/I2C2_SDA/U3_RX_30") (pintype "passive"))
    )
    (net (code "16") (name "/KOUT2") (class "Default")
      (node (ref "C48") (pin "2") (pinfunction "2_2") (pintype "passive"))
      (node (ref "R108") (pin "2") (pinfunction "2_2") (pintype "passive"))
      (node (ref "U13") (pin "7") (pinfunction "2OUT_7") (pintype "passive"))
      (node (ref "U25") (pin "36") (pinfunction "PB15/SPI2_MOSI/I2S2_SD/TIM1_CH3N_36") (pintype "passive"))
    )
    (net (code "17") (name "/KOUT3") (class "Default")
      (node (ref "C53") (pin "2") (pinfunction "2_2") (pintype "passive"))
      (node (ref "R110") (pin "2") (pinfunction "2_2") (pintype "passive"))
      (node (ref "U14") (pin "7") (pinfunction "2OUT_7") (pintype "passive"))
      (node (ref "U25") (pin "41") (pinfunction "PA8/TIM1_CH1/MCO_41") (pintype "passive"))
    )
    (net (code "18") (name "/KOUT4") (class "Default")
      (node (ref "C54") (pin "2") (pinfunction "2_2") (pintype "passive"))
      (node (ref "R111") (pin "2") (pinfunction "2_2") (pintype "passive"))
      (node (ref "U15") (pin "7") (pinfunction "2OUT_7") (pintype "passive"))
      (node (ref "U25") (pin "58") (pinfunction "PB6/I2C1_SCL/TIM4_CH1_58") (pintype "passive"))
    )
    (net (code "19") (name "/KOUT5") (class "Default")
      (node (ref "C38") (pin "2") (pinfunction "2_2") (pintype "passive"))
      (node (ref "R79") (pin "2") (pinfunction "2_2") (pintype "passive"))
      (node (ref "U18") (pin "7") (pinfunction "2OUT_7") (pintype "passive"))
      (node (ref "U25") (pin "51") (pinfunction "PC10/U4_TX/SDIO_D2_51") (pintype "passive"))
    )
    (net (code "20") (name "/LED1") (class "Default")
      (node (ref "C26") (pin "1") (pinfunction "1_1") (pintype "passive"))
      (node (ref "CH1") (pin "2") (pinfunction "2_2") (pintype "passive"))
      (node (ref "U4") (pin "5") (pinfunction "D_5") (pintype "passive"))
      (node (ref "U4") (pin "6") (pinfunction "D_6") (pintype "passive"))
      (node (ref "U4") (pin "7") (pinfunction "D_7") (pintype "passive"))
      (node (ref "U4") (pin "8") (pinfunction "D_8") (pintype "passive"))
    )
    (net (code "21") (name "/LED2") (class "Default")
      (node (ref "C32") (pin "1") (pinfunction "1_1") (pintype "passive"))
      (node (ref "CH2") (pin "2") (pinfunction "2_2") (pintype "passive"))
      (node (ref "U6") (pin "5") (pinfunction "D_5") (pintype "passive"))
      (node (ref "U6") (pin "6") (pinfunction "D_6") (pintype "passive"))
      (node (ref "U6") (pin "7") (pinfunction "D_7") (pintype "passive"))
      (node (ref "U6") (pin "8") (pinfunction "D_8") (pintype "passive"))
    )
    (net (code "22") (name "/LED3") (class "Default")
      (node (ref "C27") (pin "1") (pinfunction "1_1") (pintype "passive"))
      (node (ref "CH3") (pin "2") (pinfunction "2_2") (pintype "passive"))
      (node (ref "U5") (pin "5") (pinfunction "D_5") (pintype "passive"))
      (node (ref "U5") (pin "6") (pinfunction "D_6") (pintype "passive"))
      (node (ref "U5") (pin "7") (pinfunction "D_7") (pintype "passive"))
      (node (ref "U5") (pin "8") (pinfunction "D_8") (pintype "passive"))
    )
    (net (code "23") (name "/LED4") (class "Default")
      (node (ref "C33") (pin "1") (pinfunction "1_1") (pintype "passive"))
      (node (ref "CH4") (pin "2") (pinfunction "2_2") (pintype "passive"))
      (node (ref "U7") (pin "5") (pinfunction "D_5") (pintype "passive"))
      (node (ref "U7") (pin "6") (pinfunction "D_6") (pintype "passive"))
      (node (ref "U7") (pin "7") (pinfunction "D_7") (pintype "passive"))
      (node (ref "U7") (pin "8") (pinfunction "D_8") (pintype "passive"))
    )
    (net (code "24") (name "/LED5") (class "Default")
      (node (ref "C85") (pin "1") (pinfunction "1_1") (pintype "passive"))
      (node (ref "CH5") (pin "2") (pinfunction "2_2") (pintype "passive"))
      (node (ref "U19") (pin "5") (pinfunction "D_5") (pintype "passive"))
      (node (ref "U19") (pin "6") (pinfunction "D_6") (pintype "passive"))
      (node (ref "U19") (pin "7") (pinfunction "D_7") (pintype "passive"))
      (node (ref "U19") (pin "8") (pinfunction "D_8") (pintype "passive"))
    )
    (net (code "25") (name "/LED_TEST") (class "Default")
      (node (ref "R90") (pin "1") (pinfunction "1_1") (pintype "passive"))
      (node (ref "U25") (pin "16") (pinfunction "PA2/U2_TX/ADC2/TIM2_CH3/TIM5_CH3_16") (pintype "passive"))
    )
    (net (code "26") (name "/M1") (class "Default")
      (node (ref "C29") (pin "1") (pinfunction "1_1") (pintype "passive"))
      (node (ref "CH1") (pin "1") (pinfunction "1_1") (pintype "passive"))
      (node (ref "D2") (pin "1") (pinfunction "A_1") (pintype "passive"))
      (node (ref "D6") (pin "2") (pinfunction "K_2") (pintype "passive"))
      (node (ref "Q2") (pin "2") (pinfunction "D_2") (pintype "passive"))
      (node (ref "Q6") (pin "2") (pinfunction "D_2") (pintype "passive"))
    )
    (net (code "27") (name "/M2") (class "Default")
      (node (ref "C30") (pin "1") (pinfunction "1_1") (pintype "passive"))
      (node (ref "CH2") (pin "1") (pinfunction "1_1") (pintype "passive"))
      (node (ref "D3") (pin "1") (pinfunction "A_1") (pintype "passive"))
      (node (ref "D7") (pin "2") (pinfunction "K_2") (pintype "passive"))
      (node (ref "Q3") (pin "2") (pinfunction "D_2") (pintype "passive"))
      (node (ref "Q7") (pin "2") (pinfunction "D_2") (pintype "passive"))
    )
    (net (code "28") (name "/M3") (class "Default")
      (node (ref "C31") (pin "1") (pinfunction "1_1") (pintype "passive"))
      (node (ref "CH3") (pin "1") (pinfunction "1_1") (pintype "passive"))
      (node (ref "D4") (pin "1") (pinfunction "A_1") (pintype "passive"))
      (node (ref "D8") (pin "2") (pinfunction "K_2") (pintype "passive"))
      (node (ref "Q4") (pin "2") (pinfunction "D_2") (pintype "passive"))
      (node (ref "Q8") (pin "2") (pinfunction "D_2") (pintype "passive"))
    )
    (net (code "29") (name "/M4") (class "Default")
      (node (ref "C28") (pin "1") (pinfunction "1_1") (pintype "passive"))
      (node (ref "CH4") (pin "1") (pinfunction "1_1") (pintype "passive"))
      (node (ref "D1") (pin "1") (pinfunction "A_1") (pintype "passive"))
      (node (ref "D5") (pin "2") (pinfunction "K_2") (pintype "passive"))
      (node (ref "Q1") (pin "2") (pinfunction "D_2") (pintype "passive"))
      (node (ref "Q5") (pin "2") (pinfunction "D_2") (pintype "passive"))
    )
    (net (code "30") (name "/M5") (class "Default")
      (node (ref "C86") (pin "1") (pinfunction "1_1") (pintype "passive"))
      (node (ref "CH5") (pin "1") (pinfunction "1_1") (pintype "passive"))
      (node (ref "D10") (pin "2") (pinfunction "K_2") (pintype "passive"))
      (node (ref "D9") (pin "1") (pinfunction "A_1") (pintype "passive"))
      (node (ref "Q10") (pin "2") (pinfunction "D_2") (pintype "passive"))
      (node (ref "Q9") (pin "2") (pinfunction "D_2") (pintype "passive"))
    )
    (net (code "31") (name "/NET_RST") (class "Default")
      (node (ref "U24") (pin "4") (pinfunction "RST_4") (pintype "passive"))
      (node (ref "U25") (pin "15") (pinfunction "PA1/ADC1/TIM2_CH2/TIM5_CH2_15") (pintype "passive"))
    )
    (net (code "32") (name "/PL1") (class "Default")
      (node (ref "R3") (pin "1") (pinfunction "1_1") (pintype "passive"))
      (node (ref "U25") (pin "21") (pinfunction "PA5/SPI1_SCK/ADC5/DAC2_21") (pintype "passive"))
    )
    (net (code "33") (name "/PL2") (class "Default")
      (node (ref "R27") (pin "1") (pinfunction "1_1") (pintype "passive"))
      (node (ref "U25") (pin "22") (pinfunction "PA6/SPI1_MISO/ADC6/TIM3_CH1/TIM8_BKIN_22") (pintype "passive"))
    )
    (net (code "34") (name "/PL3") (class "Default")
      (node (ref "R4") (pin "1") (pinfunction "1_1") (pintype "passive"))
      (node (ref "U25") (pin "23") (pinfunction "PA7/SPI1_MOSI/ADC7/TIM3_CH2/TIM8_CH1N_23") (pintype "passive"))
    )
    (net (code "35") (name "/PL4") (class "Default")
      (node (ref "R28") (pin "1") (pinfunction "1_1") (pintype "passive"))
      (node (ref "U25") (pin "24") (pinfunction "PC4/ADC14_24") (pintype "passive"))
    )
    (net (code "36") (name "/PL5") (class "Default")
      (node (ref "R87") (pin "1") (pinfunction "1_1") (pintype "passive"))
      (node (ref "U25") (pin "54") (pinfunction "PD2/TIM3_ETR/U5_RX/SDIO_CMD_54") (pintype "passive"))
    )
    (net (code "37") (name "/PM1") (class "Default")
      (node (ref "R10") (pin "1") (pinfunction "1_1") (pintype "passive"))
      (node (ref "U25") (pin "8") (pinfunction "PC0/ADC10_8") (pintype "passive"))
    )
    (net (code "38") (name "/PM2") (class "Default")
      (node (ref "R11") (pin "1") (pinfunction "1_1") (pintype "passive"))
      (node (ref "U25") (pin "9") (pinfunction "PC1/ADC11_9") (pintype "passive"))
    )
    (net (code "39") (name "/PM3") (class "Default")
      (node (ref "R12") (pin "1") (pinfunction "1_1") (pintype "passive"))
      (node (ref "U25") (pin "10") (pinfunction "PC2/ADC12_10") (pintype "passive"))
    )
    (net (code "40") (name "/PM4") (class "Default")
      (node (ref "R9") (pin "1") (pinfunction "1_1") (pintype "passive"))
      (node (ref "U25") (pin "11") (pinfunction "PC3/ADC13_11") (pintype "passive"))
    )
    (net (code "41") (name "/PM5") (class "Default")
      (node (ref "R89") (pin "1") (pinfunction "1_1") (pintype "passive"))
      (node (ref "U25") (pin "53") (pinfunction "PC12/U5_TX/SDIO_CK_53") (pintype "passive"))
    )
    (net (code "42") (name "/PRUN") (class "Default")
      (node (ref "R114") (pin "1") (pinfunction "1_1") (pintype "passive"))
      (node (ref "U25") (pin "57") (pinfunction "PB5/I2C1_SMBA/SPI3_MOSI/I2S3_SD_57") (pintype "passive"))
    )
    (net (code "43") (name "/RUN") (class "Default")
      (node (ref "C87") (pin "1") (pinfunction "1_1") (pintype "passive"))
      (node (ref "CH6") (pin "1") (pinfunction "1_1") (pintype "passive"))
      (node (ref "U23") (pin "5") (pinfunction "D_5") (pintype "passive"))
      (node (ref "U23") (pin "6") (pinfunction "D_6") (pintype "passive"))
      (node (ref "U23") (pin "7") (pinfunction "D_7") (pintype "passive"))
      (node (ref "U23") (pin "8") (pinfunction "D_8") (pintype "passive"))
    )
    (net (code "44") (name "/S11") (class "Default")
      (node (ref "C56") (pin "2") (pinfunction "2_2") (pintype "passive"))
      (node (ref "R33") (pin "1") (pinfunction "1_1") (pintype "passive"))
      (node (ref "U26") (pin "15") (pinfunction "E_15") (pintype "passive"))
      (node (ref "U8") (pin "2") (pinfunction "1IN-_2") (pintype "passive"))
    )
    (net (code "45") (name "/S12") (class "Default")
      (node (ref "C64") (pin "2") (pinfunction "2_2") (pintype "passive"))
      (node (ref "R47") (pin "1") (pinfunction "1_1") (pintype "passive"))
      (node (ref "U26") (pin "13") (pinfunction "E_13") (pintype "passive"))
      (node (ref "U8") (pin "6") (pinfunction "2IN-_6") (pintype "passive"))
    )
    (net (code "46") (name "/S13") (class "Default")
      (node (ref "C60") (pin "2") (pinfunction "2_2") (pintype "passive"))
      (node (ref "R57") (pin "1") (pinfunction "1_1") (pintype "passive"))
      (node (ref "U12") (pin "2") (pinfunction "1IN-_2") (pintype "passive"))
      (node (ref "U26") (pin "11") (pinfunction "E_11") (pintype "passive"))
    )
    (net (code "47") (name "/S21") (class "Default")
      (node (ref "C57") (pin "2") (pinfunction "2_2") (pintype "passive"))
      (node (ref "R34") (pin "1") (pinfunction "1_1") (pintype "passive"))
      (node (ref "U27") (pin "15") (pinfunction "E_15") (pintype "passive"))
      (node (ref "U9") (pin "2") (pinfunction "1IN-_2") (pintype "passive"))
    )
    (net (code "48") (name "/S22") (class "Default")
      (node (ref "C65") (pin "2") (pinfunction "2_2") (pintype "passive"))
      (node (ref "R48") (pin "1") (pinfunction "1_1") (pintype "passive"))
      (node (ref "U27") (pin "13") (pinfunction "E_13") (pintype "passive"))
      (node (ref "U9") (pin "6") (pinfunction "2IN-_6") (pintype "passive"))
    )
    (net (code "49") (name "/S23") (class "Default")
      (node (ref "C61") (pin "2") (pinfunction "2_2") (pintype "passive"))
      (node (ref "R58") (pin "1") (pinfunction "1_1") (pintype "passive"))
      (node (ref "U13") (pin "2") (pinfunction "1IN-_2") (pintype "passive"))
      (node (ref "U27") (pin "11") (pinfunction "E_11") (pintype "passive"))
    )
    (net (code "50") (name "/S31") (class "Default")
      (node (ref "C58") (pin "2") (pinfunction "2_2") (pintype "passive"))
      (node (ref "R35") (pin "1") (pinfunction "1_1") (pintype "passive"))
      (node (ref "U10") (pin "2") (pinfunction "1IN-_2") (pintype "passive"))
      (node (ref "U28") (pin "15") (pinfunction "E_15") (pintype "passive"))
    )
    (net (code "51") (name "/S32") (class "Default")
      (node (ref "C66") (pin "2") (pinfunction "2_2") (pintype "passive"))
      (node (ref "R51") (pin "1") (pinfunction "1_1") (pintype "passive"))
      (node (ref "U10") (pin "6") (pinfunction "2IN-_6") (pintype "passive"))
      (node (ref "U28") (pin "13") (pinfunction "E_13") (pintype "passive"))
    )
    (net (code "52") (name "/S33") (class "Default")
      (node (ref "C62") (pin "2") (pinfunction "2_2") (pintype "passive"))
      (node (ref "R59") (pin "1") (pinfunction "1_1") (pintype "passive"))
      (node (ref "U14") (pin "2") (pinfunction "1IN-_2") (pintype "passive"))
      (node (ref "U28") (pin "11") (pinfunction "E_11") (pintype "passive"))
    )
    (net (code "53") (name "/S41") (class "Default")
      (node (ref "C59") (pin "2") (pinfunction "2_2") (pintype "passive"))
      (node (ref "R36") (pin "1") (pinfunction "1_1") (pintype "passive"))
      (node (ref "U11") (pin "2") (pinfunction "1IN-_2") (pintype "passive"))
      (node (ref "U29") (pin "15") (pinfunction "E_15") (pintype "passive"))
    )
    (net (code "54") (name "/S42") (class "Default")
      (node (ref "C67") (pin "2") (pinfunction "2_2") (pintype "passive"))
      (node (ref "R52") (pin "1") (pinfunction "1_1") (pintype "passive"))
      (node (ref "U11") (pin "6") (pinfunction "2IN-_6") (pintype "passive"))
      (node (ref "U29") (pin "13") (pinfunction "E_13") (pintype "passive"))
    )
    (net (code "55") (name "/S43") (class "Default")
      (node (ref "C63") (pin "2") (pinfunction "2_2") (pintype "passive"))
      (node (ref "R60") (pin "1") (pinfunction "1_1") (pintype "passive"))
      (node (ref "U15") (pin "2") (pinfunction "1IN-_2") (pintype "passive"))
      (node (ref "U29") (pin "11") (pinfunction "E_11") (pintype "passive"))
    )
    (net (code "56") (name "/S51") (class "Default")
      (node (ref "C25") (pin "2") (pinfunction "2_2") (pintype "passive"))
      (node (ref "R20") (pin "1") (pinfunction "1_1") (pintype "passive"))
      (node (ref "U16") (pin "15") (pinfunction "E_15") (pintype "passive"))
      (node (ref "U17") (pin "2") (pinfunction "1IN-_2") (pintype "passive"))
    )
    (net (code "57") (name "/S52") (class "Default")
      (node (ref "C37") (pin "2") (pinfunction "2_2") (pintype "passive"))
      (node (ref "R25") (pin "1") (pinfunction "1_1") (pintype "passive"))
      (node (ref "U16") (pin "13") (pinfunction "E_13") (pintype "passive"))
      (node (ref "U17") (pin "6") (pinfunction "2IN-_6") (pintype "passive"))
    )
    (net (code "58") (name "/S53") (class "Default")
      (node (ref "C55") (pin "2") (pinfunction "2_2") (pintype "passive"))
      (node (ref "R80") (pin "1") (pinfunction "1_1") (pintype "passive"))
      (node (ref "U16") (pin "11") (pinfunction "E_11") (pintype "passive"))
      (node (ref "U18") (pin "2") (pinfunction "1IN-_2") (pintype "passive"))
    )
    (net (code "59") (name "/SIN11") (class "Default")
      (node (ref "C68") (pin "2") (pinfunction "2_2") (pintype "passive"))
      (node (ref "CH1") (pin "4") (pinfunction "4_4") (pintype "passive"))
      (node (ref "R29") (pin "1") (pinfunction "1_1") (pintype "passive"))
    )
    (net (code "60") (name "/SIN12") (class "Default")
      (node (ref "C88") (pin "2") (pinfunction "2_2") (pintype "passive"))
      (node (ref "CH1") (pin "5") (pinfunction "5_5") (pintype "passive"))
      (node (ref "R38") (pin "1") (pinfunction "1_1") (pintype "passive"))
    )
    (net (code "61") (name "/SIN13") (class "Default")
      (node (ref "C72") (pin "2") (pinfunction "2_2") (pintype "passive"))
      (node (ref "CH1") (pin "6") (pinfunction "6_6") (pintype "passive"))
      (node (ref "R53") (pin "1") (pinfunction "1_1") (pintype "passive"))
    )
    (net (code "62") (name "/SIN21") (class "Default")
      (node (ref "C71") (pin "1") (pinfunction "1_1") (pintype "passive"))
      (node (ref "CH2") (pin "4") (pinfunction "4_4") (pintype "passive"))
      (node (ref "R30") (pin "1") (pinfunction "1_1") (pintype "passive"))
    )
    (net (code "63") (name "/SIN22") (class "Default")
      (node (ref "C89") (pin "2") (pinfunction "2_2") (pintype "passive"))
      (node (ref "CH2") (pin "5") (pinfunction "5_5") (pintype "passive"))
      (node (ref "R40") (pin "1") (pinfunction "1_1") (pintype "passive"))
    )
    (net (code "64") (name "/SIN23") (class "Default")
      (node (ref "C75") (pin "1") (pinfunction "1_1") (pintype "passive"))
      (node (ref "CH2") (pin "6") (pinfunction "6_6") (pintype "passive"))
      (node (ref "R54") (pin "1") (pinfunction "1_1") (pintype "passive"))
    )
    (net (code "65") (name "/SIN31") (class "Default")
      (node (ref "C69") (pin "1") (pinfunction "1_1") (pintype "passive"))
      (node (ref "CH3") (pin "4") (pinfunction "4_4") (pintype "passive"))
      (node (ref "R31") (pin "1") (pinfunction "1_1") (pintype "passive"))
    )
    (net (code "66") (name "/SIN32") (class "Default")
      (node (ref "C90") (pin "2") (pinfunction "2_2") (pintype "passive"))
      (node (ref "CH3") (pin "5") (pinfunction "5_5") (pintype "passive"))
      (node (ref "R42") (pin "1") (pinfunction "1_1") (pintype "passive"))
    )
    (net (code "67") (name "/SIN33") (class "Default")
      (node (ref "C73") (pin "1") (pinfunction "1_1") (pintype "passive"))
      (node (ref "CH3") (pin "6") (pinfunction "6_6") (pintype "passive"))
      (node (ref "R55") (pin "1") (pinfunction "1_1") (pintype "passive"))
    )
    (net (code "68") (name "/SIN41") (class "Default")
      (node (ref "C70") (pin "1") (pinfunction "1_1") (pintype "passive"))
      (node (ref "CH4") (pin "4") (pinfunction "4_4") (pintype "passive"))
      (node (ref "R32") (pin "1") (pinfunction "1_1") (pintype "passive"))
    )
    (net (code "69") (name "/SIN42") (class "Default")
      (node (ref "C91") (pin "2") (pinfunction "2_2") (pintype "passive"))
      (node (ref "CH4") (pin "5") (pinfunction "5_5") (pintype "passive"))
      (node (ref "R44") (pin "1") (pinfunction "1_1") (pintype "passive"))
    )
    (net (code "70") (name "/SIN43") (class "Default")
      (node (ref "C74") (pin "1") (pinfunction "1_1") (pintype "passive"))
      (node (ref "CH4") (pin "6") (pinfunction "6_6") (pintype "passive"))
      (node (ref "R56") (pin "1") (pinfunction "1_1") (pintype "passive"))
    )
    (net (code "71") (name "/SIN51") (class "Default")
      (node (ref "C92") (pin "2") (pinfunction "2_2") (pintype "passive"))
      (node (ref "CH5") (pin "4") (pinfunction "4_4") (pintype "passive"))
      (node (ref "R17") (pin "1") (pinfunction "1_1") (pintype "passive"))
    )
    (net (code "72") (name "/SIN52") (class "Default")
      (node (ref "C93") (pin "2") (pinfunction "2_2") (pintype "passive"))
      (node (ref "CH5") (pin "5") (pinfunction "5_5") (pintype "passive"))
      (node (ref "R22") (pin "1") (pinfunction "1_1") (pintype "passive"))
    )
    (net (code "73") (name "/SIN53") (class "Default")
      (node (ref "C94") (pin "2") (pinfunction "2_2") (pintype "passive"))
      (node (ref "CH5") (pin "6") (pinfunction "6_6") (pintype "passive"))
      (node (ref "R77") (pin "1") (pinfunction "1_1") (pintype "passive"))
    )
    (net (code "74") (name "/SOUT11") (class "Default")
      (node (ref "C39") (pin "2") (pinfunction "2_2") (pintype "passive"))
      (node (ref "R96") (pin "2") (pinfunction "2_2") (pintype "passive"))
      (node (ref "U25") (pin "26") (pinfunction "PB0/ADC8/TIM3_CH3/TIM8_CH2N_26") (pintype "passive"))
      (node (ref "U8") (pin "1") (pinfunction "1OUT_1") (pintype "passive"))
    )
    (net (code "75") (name "/SOUT12") (class "Default")
      (node (ref "C41") (pin "2") (pinfunction "2_2") (pintype "passive"))
      (node (ref "R97") (pin "2") (pinfunction "2_2") (pintype "passive"))
      (node (ref "U25") (pin "27") (pinfunction "PB1/ADC9/TIM3_CH4/TIM8_CH3N_27") (pintype "passive"))
      (node (ref "U8") (pin "7") (pinfunction "2OUT_7") (pintype "passive"))
    )
    (net (code "76") (name "/SOUT13") (class "Default")
      (node (ref "C49") (pin "2") (pinfunction "2_2") (pintype "passive"))
      (node (ref "R104") (pin "2") (pinfunction "2_2") (pintype "passive"))
      (node (ref "U12") (pin "1") (pinfunction "1OUT_1") (pintype "passive"))
      (node (ref "U25") (pin "29") (pinfunction "PB10/I2C2_SCL/U3_TX_29") (pintype "passive"))
    )
    (net (code "77") (name "/SOUT21") (class "Default")
      (node (ref "C40") (pin "2") (pinfunction "2_2") (pintype "passive"))
      (node (ref "R98") (pin "2") (pinfunction "2_2") (pintype "passive"))
      (node (ref "U25") (pin "33") (pinfunction "PB12/SPI2_NSS/I2S2_WS/I2C2_SMBAI/TIM1_BKIN_33") (pintype "passive"))
      (node (ref "U9") (pin "1") (pinfunction "1OUT_1") (pintype "passive"))
    )
    (net (code "78") (name "/SOUT22") (class "Default")
      (node (ref "C44") (pin "2") (pinfunction "2_2") (pintype "passive"))
      (node (ref "R101") (pin "2") (pinfunction "2_2") (pintype "passive"))
      (node (ref "U25") (pin "34") (pinfunction "PB13/SPI2_SCK/I2S2_CK/TIM1_CH1N_34") (pintype "passive"))
      (node (ref "U9") (pin "7") (pinfunction "2OUT_7") (pintype "passive"))
    )
    (net (code "79") (name "/SOUT23") (class "Default")
      (node (ref "C50") (pin "2") (pinfunction "2_2") (pintype "passive"))
      (node (ref "R105") (pin "2") (pinfunction "2_2") (pintype "passive"))
      (node (ref "U13") (pin "1") (pinfunction "1OUT_1") (pintype "passive"))
      (node (ref "U25") (pin "35") (pinfunction "PB14/SPI2_MISO/TIM1_CH2N_35") (pintype "passive"))
    )
    (net (code "80") (name "/SOUT31") (class "Default")
      (node (ref "C42") (pin "2") (pinfunction "2_2") (pintype "passive"))
      (node (ref "R99") (pin "2") (pinfunction "2_2") (pintype "passive"))
      (node (ref "U10") (pin "1") (pinfunction "1OUT_1") (pintype "passive"))
      (node (ref "U25") (pin "37") (pinfunction "PC6/I2S2_MCK/TIM8_CH1/SDIO_D6_37") (pintype "passive"))
    )
    (net (code "81") (name "/SOUT32") (class "Default")
      (node (ref "C45") (pin "2") (pinfunction "2_2") (pintype "passive"))
      (node (ref "R102") (pin "2") (pinfunction "2_2") (pintype "passive"))
      (node (ref "U10") (pin "7") (pinfunction "2OUT_7") (pintype "passive"))
      (node (ref "U25") (pin "38") (pinfunction "PC7/I2S3_MCK/TIM8_CH2/SDIO_D7_38") (pintype "passive"))
    )
    (net (code "82") (name "/SOUT33") (class "Default")
      (node (ref "C51") (pin "2") (pinfunction "2_2") (pintype "passive"))
      (node (ref "R106") (pin "2") (pinfunction "2_2") (pintype "passive"))
      (node (ref "U14") (pin "1") (pinfunction "1OUT_1") (pintype "passive"))
      (node (ref "U25") (pin "39") (pinfunction "PC8/TIM8_CH3/SDIO_D0_39") (pintype "passive"))
    )
    (net (code "83") (name "/SOUT41") (class "Default")
      (node (ref "C43") (pin "2") (pinfunction "2_2") (pintype "passive"))
      (node (ref "R100") (pin "2") (pinfunction "2_2") (pintype "passive"))
      (node (ref "U11") (pin "1") (pinfunction "1OUT_1") (pintype "passive"))
      (node (ref "U25") (pin "55") (pinfunction "PB3/JTDO/SPI3_SCK/I2S3_CK_55") (pintype "passive"))
    )
    (net (code "84") (name "/SOUT42") (class "Default")
      (node (ref "C46") (pin "2") (pinfunction "2_2") (pintype "passive"))
      (node (ref "R103") (pin "2") (pinfunction "2_2") (pintype "passive"))
      (node (ref "U11") (pin "7") (pinfunction "2OUT_7") (pintype "passive"))
      (node (ref "U25") (pin "44") (pinfunction "PA11/CAN_RX/USBDM/TIM1_CH4_44") (pintype "passive"))
    )
    (net (code "85") (name "/SOUT43") (class "Default")
      (node (ref "C52") (pin "2") (pinfunction "2_2") (pintype "passive"))
      (node (ref "R107") (pin "2") (pinfunction "2_2") (pintype "passive"))
      (node (ref "U15") (pin "1") (pinfunction "1OUT_1") (pintype "passive"))
      (node (ref "U25") (pin "56") (pinfunction "PB4/JNTRST/SPI3_MISO_56") (pintype "passive"))
    )
    (net (code "86") (name "/SOUT51") (class "Default")
      (node (ref "C34") (pin "2") (pinfunction "2_2") (pintype "passive"))
      (node (ref "R18") (pin "2") (pinfunction "2_2") (pintype "passive"))
      (node (ref "U17") (pin "1") (pinfunction "1OUT_1") (pintype "passive"))
      (node (ref "U25") (pin "25") (pinfunction "PC5/ADC15_25") (pintype "passive"))
    )
    (net (code "87") (name "/SOUT52") (class "Default")
      (node (ref "C35") (pin "2") (pinfunction "2_2") (pintype "passive"))
      (node (ref "R19") (pin "2") (pinfunction "2_2") (pintype "passive"))
      (node (ref "U17") (pin "7") (pinfunction "2OUT_7") (pintype "passive"))
      (node (ref "U25") (pin "52") (pinfunction "PC11/U4_RX/SDIO_D3_52") (pintype "passive"))
    )
    (net (code "88") (name "/SOUT53") (class "Default")
      (node (ref "C80") (pin "2") (pinfunction "2_2") (pintype "passive"))
      (node (ref "R78") (pin "2") (pinfunction "2_2") (pintype "passive"))
      (node (ref "U18") (pin "1") (pinfunction "1OUT_1") (pintype "passive"))
      (node (ref "U25") (pin "40") (pinfunction "PC9/TIM8_CH4/SDIO_D1_40") (pintype "passive"))
    )
    (net (code "89") (name "/TCK{slash}SWCLK") (class "Default")
      (node (ref "JP1") (pin "3") (pinfunction "3_3") (pintype "passive"))
      (node (ref "U25") (pin "49") (pinfunction "PA14/JTCK/SWCLK_49") (pintype "passive"))
    )
    (net (code "90") (name "/TMS{slash}SWDIO") (class "Default")
      (node (ref "JP1") (pin "2") (pinfunction "2_2") (pintype "passive"))
      (node (ref "U25") (pin "46") (pinfunction "PA13/JTMS/SWDIO_46") (pintype "passive"))
    )
    (net (code "91") (name "/USAR1_RXD") (class "Default")
      (node (ref "U24") (pin "9") (pinfunction "TXD_9") (pintype "passive"))
      (node (ref "U25") (pin "43") (pinfunction "PA10/U1_RX/TIM1_CH3_43") (pintype "passive"))
    )
    (net (code "92") (name "/USAR1_TXD") (class "Default")
      (node (ref "U24") (pin "8") (pinfunction "RXD_8") (pintype "passive"))
      (node (ref "U25") (pin "42") (pinfunction "PA9/U1_TX/TIM1_CH2_42") (pintype "passive"))
    )
    (net (code "93") (name "24V0") (class "Default")
      (node (ref "C10") (pin "2") (pinfunction "2_2") (pintype "passive"))
      (node (ref "C13") (pin "1") (pinfunction "1_1") (pintype "passive"))
      (node (ref "C26") (pin "2") (pinfunction "2_2") (pintype "passive"))
      (node (ref "C27") (pin "2") (pinfunction "2_2") (pintype "passive"))
      (node (ref "C28") (pin "2") (pinfunction "2_2") (pintype "passive"))
      (node (ref "C29") (pin "2") (pinfunction "2_2") (pintype "passive"))
      (node (ref "C30") (pin "2") (pinfunction "2_2") (pintype "passive"))
      (node (ref "C31") (pin "2") (pinfunction "2_2") (pintype "passive"))
      (node (ref "C32") (pin "2") (pinfunction "2_2") (pintype "passive"))
      (node (ref "C33") (pin "2") (pinfunction "2_2") (pintype "passive"))
      (node (ref "C68") (pin "1") (pinfunction "1_1") (pintype "passive"))
      (node (ref "C69") (pin "2") (pinfunction "2_2") (pintype "passive"))
      (node (ref "C70") (pin "2") (pinfunction "2_2") (pintype "passive"))
      (node (ref "C71") (pin "2") (pinfunction "2_2") (pintype "passive"))
      (node (ref "C72") (pin "1") (pinfunction "1_1") (pintype "passive"))
      (node (ref "C73") (pin "2") (pinfunction "2_2") (pintype "passive"))
      (node (ref "C74") (pin "2") (pinfunction "2_2") (pintype "passive"))
      (node (ref "C75") (pin "2") (pinfunction "2_2") (pintype "passive"))
      (node (ref "C85") (pin "2") (pinfunction "2_2") (pintype "passive"))
      (node (ref "C86") (pin "2") (pinfunction "2_2") (pintype "passive"))
      (node (ref "C87") (pin "2") (pinfunction "2_2") (pintype "passive"))
      (node (ref "C88") (pin "1") (pinfunction "1_1") (pintype "passive"))
      (node (ref "C89") (pin "1") (pinfunction "1_1") (pintype "passive"))
      (node (ref "C90") (pin "1") (pinfunction "1_1") (pintype "passive"))
      (node (ref "C91") (pin "1") (pinfunction "1_1") (pintype "passive"))
      (node (ref "C92") (pin "1") (pinfunction "1_1") (pintype "passive"))
      (node (ref "C93") (pin "1") (pinfunction "1_1") (pintype "passive"))
      (node (ref "C94") (pin "1") (pinfunction "1_1") (pintype "passive"))
      (node (ref "CH1") (pin "8") (pinfunction "8_8") (pintype "passive"))
      (node (ref "CH2") (pin "8") (pinfunction "8_8") (pintype "passive"))
      (node (ref "CH25") (pin "2") (pinfunction "2_2") (pintype "passive"))
      (node (ref "CH25") (pin "4") (pinfunction "4_4") (pintype "passive"))
      (node (ref "CH3") (pin "8") (pinfunction "8_8") (pintype "passive"))
      (node (ref "CH4") (pin "8") (pinfunction "8_8") (pintype "passive"))
      (node (ref "CH5") (pin "8") (pinfunction "8_8") (pintype "passive"))
      (node (ref "CH6") (pin "2") (pinfunction "2_2") (pintype "passive"))
      (node (ref "D10") (pin "1") (pinfunction "A_1") (pintype "passive"))
      (node (ref "D5") (pin "1") (pinfunction "A_1") (pintype "passive"))
      (node (ref "D6") (pin "1") (pinfunction "A_1") (pintype "passive"))
      (node (ref "D7") (pin "1") (pinfunction "A_1") (pintype "passive"))
      (node (ref "D8") (pin "1") (pinfunction "A_1") (pintype "passive"))
      (node (ref "LED2") (pin "2") (pinfunction "K_2") (pintype "passive"))
      (node (ref "Q10") (pin "3") (pinfunction "S_3") (pintype "passive"))
      (node (ref "Q5") (pin "3") (pinfunction "S_3") (pintype "passive"))
      (node (ref "Q6") (pin "3") (pinfunction "S_3") (pintype "passive"))
      (node (ref "Q7") (pin "3") (pinfunction "S_3") (pintype "passive"))
      (node (ref "Q8") (pin "3") (pinfunction "S_3") (pintype "passive"))
      (node (ref "U1") (pin "11") (pinfunction "E_11") (pintype "passive"))
      (node (ref "U1") (pin "13") (pinfunction "E_13") (pintype "passive"))
      (node (ref "U1") (pin "15") (pinfunction "E_15") (pintype "passive"))
      (node (ref "U1") (pin "9") (pinfunction "E_9") (pintype "passive"))
      (node (ref "U16") (pin "2") (pinfunction "K_2") (pintype "passive"))
      (node (ref "U16") (pin "4") (pinfunction "K_4") (pintype "passive"))
      (node (ref "U16") (pin "6") (pinfunction "K_6") (pintype "passive"))
      (node (ref "U16") (pin "8") (pinfunction "K_8") (pintype "passive"))
      (node (ref "U2") (pin "11") (pinfunction "E_11") (pintype "passive"))
      (node (ref "U2") (pin "13") (pinfunction "E_13") (pintype "passive"))
      (node (ref "U2") (pin "15") (pinfunction "E_15") (pintype "passive"))
      (node (ref "U2") (pin "9") (pinfunction "E_9") (pintype "passive"))
      (node (ref "U21") (pin "1") (pinfunction "GND_1") (pintype "passive"))
      (node (ref "U22") (pin "11") (pinfunction "E_11") (pintype "passive"))
      (node (ref "U22") (pin "13") (pinfunction "E_13") (pintype "passive"))
      (node (ref "U22") (pin "15") (pinfunction "E_15") (pintype "passive"))
      (node (ref "U22") (pin "9") (pinfunction "E_9") (pintype "passive"))
      (node (ref "U26") (pin "2") (pinfunction "K_2") (pintype "passive"))
      (node (ref "U26") (pin "4") (pinfunction "K_4") (pintype "passive"))
      (node (ref "U26") (pin "6") (pinfunction "K_6") (pintype "passive"))
      (node (ref "U26") (pin "8") (pinfunction "K_8") (pintype "passive"))
      (node (ref "U27") (pin "2") (pinfunction "K_2") (pintype "passive"))
      (node (ref "U27") (pin "4") (pinfunction "K_4") (pintype "passive"))
      (node (ref "U27") (pin "6") (pinfunction "K_6") (pintype "passive"))
      (node (ref "U27") (pin "8") (pinfunction "K_8") (pintype "passive"))
      (node (ref "U28") (pin "2") (pinfunction "K_2") (pintype "passive"))
      (node (ref "U28") (pin "4") (pinfunction "K_4") (pintype "passive"))
      (node (ref "U28") (pin "6") (pinfunction "K_6") (pintype "passive"))
      (node (ref "U28") (pin "8") (pinfunction "K_8") (pintype "passive"))
      (node (ref "U29") (pin "2") (pinfunction "K_2") (pintype "passive"))
      (node (ref "U29") (pin "4") (pinfunction "K_4") (pintype "passive"))
      (node (ref "U29") (pin "6") (pinfunction "K_6") (pintype "passive"))
      (node (ref "U29") (pin "8") (pinfunction "K_8") (pintype "passive"))
      (node (ref "U3") (pin "11") (pinfunction "E_11") (pintype "passive"))
      (node (ref "U3") (pin "13") (pinfunction "E_13") (pintype "passive"))
      (node (ref "U3") (pin "15") (pinfunction "E_15") (pintype "passive"))
      (node (ref "U3") (pin "9") (pinfunction "E_9") (pintype "passive"))
    )
    (net (code "94") (name "GND") (class "Default")
      (node (ref "C1") (pin "1") (pinfunction "1_1") (pintype "passive"))
      (node (ref "C11") (pin "1") (pinfunction "1_1") (pintype "passive"))
      (node (ref "C12") (pin "2") (pinfunction "2_2") (pintype "passive"))
      (node (ref "C14") (pin "2") (pinfunction "2_2") (pintype "passive"))
      (node (ref "C15") (pin "1") (pinfunction "1_1") (pintype "passive"))
      (node (ref "C16") (pin "2") (pinfunction "2_2") (pintype "passive"))
      (node (ref "C17") (pin "1") (pinfunction "1_1") (pintype "passive"))
      (node (ref "C18") (pin "1") (pinfunction "1_1") (pintype "passive"))
      (node (ref "C19") (pin "1") (pinfunction "1_1") (pintype "passive"))
      (node (ref "C2") (pin "1") (pinfunction "1_1") (pintype "passive"))
      (node (ref "C20") (pin "2") (pinfunction "2_2") (pintype "passive"))
      (node (ref "C21") (pin "1") (pinfunction "1_1") (pintype "passive"))
      (node (ref "C22") (pin "2") (pinfunction "2_2") (pintype "passive"))
      (node (ref "C23") (pin "1") (pinfunction "1_1") (pintype "passive"))
      (node (ref "C24") (pin "1") (pinfunction "1_1") (pintype "passive"))
      (node (ref "C25") (pin "1") (pinfunction "1_1") (pintype "passive"))
      (node (ref "C3") (pin "1") (pinfunction "1_1") (pintype "passive"))
      (node (ref "C34") (pin "1") (pinfunction "1_1") (pintype "passive"))
      (node (ref "C35") (pin "1") (pinfunction "1_1") (pintype "passive"))
      (node (ref "C36") (pin "1") (pinfunction "1_1") (pintype "passive"))
      (node (ref "C37") (pin "1") (pinfunction "1_1") (pintype "passive"))
      (node (ref "C38") (pin "1") (pinfunction "1_1") (pintype "passive"))
      (node (ref "C39") (pin "1") (pinfunction "1_1") (pintype "passive"))
      (node (ref "C4") (pin "1") (pinfunction "1_1") (pintype "passive"))
      (node (ref "C40") (pin "1") (pinfunction "1_1") (pintype "passive"))
      (node (ref "C41") (pin "1") (pinfunction "1_1") (pintype "passive"))
      (node (ref "C42") (pin "1") (pinfunction "1_1") (pintype "passive"))
      (node (ref "C43") (pin "1") (pinfunction "1_1") (pintype "passive"))
      (node (ref "C44") (pin "1") (pinfunction "1_1") (pintype "passive"))
      (node (ref "C45") (pin "1") (pinfunction "1_1") (pintype "passive"))
      (node (ref "C46") (pin "1") (pinfunction "1_1") (pintype "passive"))
      (node (ref "C47") (pin "1") (pinfunction "1_1") (pintype "passive"))
      (node (ref "C48") (pin "1") (pinfunction "1_1") (pintype "passive"))
      (node (ref "C49") (pin "1") (pinfunction "1_1") (pintype "passive"))
      (node (ref "C5") (pin "1") (pinfunction "1_1") (pintype "passive"))
      (node (ref "C50") (pin "1") (pinfunction "1_1") (pintype "passive"))
      (node (ref "C51") (pin "1") (pinfunction "1_1") (pintype "passive"))
      (node (ref "C52") (pin "1") (pinfunction "1_1") (pintype "passive"))
      (node (ref "C53") (pin "1") (pinfunction "1_1") (pintype "passive"))
      (node (ref "C54") (pin "1") (pinfunction "1_1") (pintype "passive"))
      (node (ref "C55") (pin "1") (pinfunction "1_1") (pintype "passive"))
      (node (ref "C56") (pin "1") (pinfunction "1_1") (pintype "passive"))
      (node (ref "C57") (pin "1") (pinfunction "1_1") (pintype "passive"))
      (node (ref "C58") (pin "1") (pinfunction "1_1") (pintype "passive"))
      (node (ref "C59") (pin "1") (pinfunction "1_1") (pintype "passive"))
      (node (ref "C6") (pin "1") (pinfunction "1_1") (pintype "passive"))
      (node (ref "C60") (pin "1") (pinfunction "1_1") (pintype "passive"))
      (node (ref "C61") (pin "1") (pinfunction "1_1") (pintype "passive"))
      (node (ref "C62") (pin "1") (pinfunction "1_1") (pintype "passive"))
      (node (ref "C63") (pin "1") (pinfunction "1_1") (pintype "passive"))
      (node (ref "C64") (pin "1") (pinfunction "1_1") (pintype "passive"))
      (node (ref "C65") (pin "1") (pinfunction "1_1") (pintype "passive"))
      (node (ref "C66") (pin "1") (pinfunction "1_1") (pintype "passive"))
      (node (ref "C67") (pin "1") (pinfunction "1_1") (pintype "passive"))
      (node (ref "C7") (pin "1") (pinfunction "1_1") (pintype "passive"))
      (node (ref "C76") (pin "1") (pinfunction "1_1") (pintype "passive"))
      (node (ref "C77") (pin "1") (pinfunction "1_1") (pintype "passive"))
      (node (ref "C78") (pin "1") (pinfunction "1_1") (pintype "passive"))
      (node (ref "C79") (pin "1") (pinfunction "1_1") (pintype "passive"))
      (node (ref "C8") (pin "1") (pinfunction "1_1") (pintype "passive"))
      (node (ref "C80") (pin "1") (pinfunction "1_1") (pintype "passive"))
      (node (ref "C81") (pin "2") (pinfunction "2_2") (pintype "passive"))
      (node (ref "C82") (pin "1") (pinfunction "1_1") (pintype "passive"))
      (node (ref "C83") (pin "1") (pinfunction "1_1") (pintype "passive"))
      (node (ref "C84") (pin "1") (pinfunction "1_1") (pintype "passive"))
      (node (ref "JP1") (pin "4") (pinfunction "4_4") (pintype "passive"))
      (node (ref "LED1") (pin "2") (pinfunction "K_2") (pintype "passive"))
      (node (ref "R20") (pin "2") (pinfunction "2_2") (pintype "passive"))
      (node (ref "R24") (pin "2") (pinfunction "2_2") (pintype "passive"))
      (node (ref "R25") (pin "2") (pinfunction "2_2") (pintype "passive"))
      (node (ref "R33") (pin "2") (pinfunction "2_2") (pintype "passive"))
      (node (ref "R34") (pin "2") (pinfunction "2_2") (pintype "passive"))
      (node (ref "R35") (pin "2") (pinfunction "2_2") (pintype "passive"))
      (node (ref "R36") (pin "2") (pinfunction "2_2") (pintype "passive"))
      (node (ref "R45") (pin "2") (pinfunction "2_2") (pintype "passive"))
      (node (ref "R46") (pin "2") (pinfunction "2_2") (pintype "passive"))
      (node (ref "R47") (pin "2") (pinfunction "2_2") (pintype "passive"))
      (node (ref "R48") (pin "2") (pinfunction "2_2") (pintype "passive"))
      (node (ref "R49") (pin "2") (pinfunction "2_2") (pintype "passive"))
      (node (ref "R50") (pin "2") (pinfunction "2_2") (pintype "passive"))
      (node (ref "R51") (pin "2") (pinfunction "2_2") (pintype "passive"))
      (node (ref "R52") (pin "2") (pinfunction "2_2") (pintype "passive"))
      (node (ref "R57") (pin "2") (pinfunction "2_2") (pintype "passive"))
      (node (ref "R58") (pin "2") (pinfunction "2_2") (pintype "passive"))
      (node (ref "R59") (pin "2") (pinfunction "2_2") (pintype "passive"))
      (node (ref "R60") (pin "2") (pinfunction "2_2") (pintype "passive"))
      (node (ref "R69") (pin "2") (pinfunction "2_2") (pintype "passive"))
      (node (ref "R70") (pin "2") (pinfunction "2_2") (pintype "passive"))
      (node (ref "R71") (pin "2") (pinfunction "2_2") (pintype "passive"))
      (node (ref "R72") (pin "2") (pinfunction "2_2") (pintype "passive"))
      (node (ref "R73") (pin "2") (pinfunction "2_2") (pintype "passive"))
      (node (ref "R74") (pin "2") (pinfunction "2_2") (pintype "passive"))
      (node (ref "R75") (pin "2") (pinfunction "2_2") (pintype "passive"))
      (node (ref "R76") (pin "2") (pinfunction "2_2") (pintype "passive"))
      (node (ref "R80") (pin "2") (pinfunction "2_2") (pintype "passive"))
      (node (ref "R82") (pin "2") (pinfunction "2_2") (pintype "passive"))
      (node (ref "R85") (pin "2") (pinfunction "2_2") (pintype "passive"))
      (node (ref "R91") (pin "1") (pinfunction "1_1") (pintype "passive"))
      (node (ref "R94") (pin "1") (pinfunction "1_1") (pintype "passive"))
      (node (ref "U1") (pin "2") (pinfunction "K_2") (pintype "passive"))
      (node (ref "U1") (pin "4") (pinfunction "K_4") (pintype "passive"))
      (node (ref "U1") (pin "6") (pinfunction "K_6") (pintype "passive"))
      (node (ref "U1") (pin "8") (pinfunction "K_8") (pintype "passive"))
      (node (ref "U10") (pin "4") (pinfunction "GND_4") (pintype "passive"))
      (node (ref "U11") (pin "4") (pinfunction "GND_4") (pintype "passive"))
      (node (ref "U12") (pin "4") (pinfunction "GND_4") (pintype "passive"))
      (node (ref "U13") (pin "4") (pinfunction "GND_4") (pintype "passive"))
      (node (ref "U14") (pin "4") (pinfunction "GND_4") (pintype "passive"))
      (node (ref "U15") (pin "4") (pinfunction "GND_4") (pintype "passive"))
      (node (ref "U17") (pin "4") (pinfunction "GND_4") (pintype "passive"))
      (node (ref "U18") (pin "4") (pinfunction "GND_4") (pintype "passive"))
      (node (ref "U2") (pin "2") (pinfunction "K_2") (pintype "passive"))
      (node (ref "U2") (pin "4") (pinfunction "K_4") (pintype "passive"))
      (node (ref "U2") (pin "6") (pinfunction "K_6") (pintype "passive"))
      (node (ref "U2") (pin "8") (pinfunction "K_8") (pintype "passive"))
      (node (ref "U20") (pin "1") (pinfunction "GND_1") (pintype "passive"))
      (node (ref "U21") (pin "4") (pinfunction "0V_4") (pintype "passive"))
      (node (ref "U22") (pin "2") (pinfunction "K_2") (pintype "passive"))
      (node (ref "U22") (pin "4") (pinfunction "K_4") (pintype "passive"))
      (node (ref "U22") (pin "6") (pinfunction "K_6") (pintype "passive"))
      (node (ref "U22") (pin "8") (pinfunction "K_8") (pintype "passive"))
      (node (ref "U24") (pin "10") (pinfunction "GND_10") (pintype "passive"))
      (node (ref "U25") (pin "12") (pinfunction "VSSA_12") (pintype "passive"))
      (node (ref "U25") (pin "18") (pinfunction "VSS_18") (pintype "passive"))
      (node (ref "U25") (pin "63") (pinfunction "VSS_63") (pintype "passive"))
      (node (ref "U3") (pin "2") (pinfunction "K_2") (pintype "passive"))
      (node (ref "U3") (pin "4") (pinfunction "K_4") (pintype "passive"))
      (node (ref "U3") (pin "6") (pinfunction "K_6") (pintype "passive"))
      (node (ref "U3") (pin "8") (pinfunction "K_8") (pintype "passive"))
      (node (ref "U8") (pin "4") (pinfunction "GND_4") (pintype "passive"))
      (node (ref "U9") (pin "4") (pinfunction "GND_4") (pintype "passive"))
    )
    (net (code "95") (name "Net-(C81-Pad1)") (class "Default")
      (node (ref "C81") (pin "1") (pinfunction "1_1") (pintype "passive"))
      (node (ref "U25") (pin "47") (pinfunction "VSS_47") (pintype "passive"))
    )
    (net (code "96") (name "Net-(C82-Pad2)") (class "Default")
      (node (ref "C82") (pin "2") (pinfunction "2_2") (pintype "passive"))
      (node (ref "U25") (pin "31") (pinfunction "VSS_31") (pintype "passive"))
    )
    (net (code "97") (name "Net-(LED1-A)") (class "Default")
      (node (ref "LED1") (pin "1") (pinfunction "A_1") (pintype "passive"))
      (node (ref "R84") (pin "1") (pinfunction "1_1") (pintype "passive"))
    )
    (net (code "98") (name "Net-(LED2-A)") (class "Default")
      (node (ref "LED2") (pin "1") (pinfunction "A_1") (pintype "passive"))
      (node (ref "R95") (pin "1") (pinfunction "1_1") (pintype "passive"))
    )
    (net (code "99") (name "Net-(LED3-K)") (class "Default")
      (node (ref "LED3") (pin "2") (pinfunction "K_2") (pintype "passive"))
      (node (ref "R90") (pin "2") (pinfunction "2_2") (pintype "passive"))
    )
    (net (code "100") (name "Net-(Q1-G)") (class "Default")
      (node (ref "Q1") (pin "1") (pinfunction "G_1") (pintype "passive"))
      (node (ref "R5") (pin "1") (pinfunction "1_1") (pintype "passive"))
      (node (ref "U2") (pin "12") (pinfunction "C_12") (pintype "passive"))
    )
    (net (code "101") (name "Net-(Q2-G)") (class "Default")
      (node (ref "Q2") (pin "1") (pinfunction "G_1") (pintype "passive"))
      (node (ref "R6") (pin "1") (pinfunction "1_1") (pintype "passive"))
      (node (ref "U1") (pin "16") (pinfunction "C_16") (pintype "passive"))
    )
    (net (code "102") (name "Net-(Q3-G)") (class "Default")
      (node (ref "Q3") (pin "1") (pinfunction "G_1") (pintype "passive"))
      (node (ref "R7") (pin "1") (pinfunction "1_1") (pintype "passive"))
      (node (ref "U1") (pin "12") (pinfunction "C_12") (pintype "passive"))
    )
    (net (code "103") (name "Net-(Q4-G)") (class "Default")
      (node (ref "Q4") (pin "1") (pinfunction "G_1") (pintype "passive"))
      (node (ref "R8") (pin "1") (pinfunction "1_1") (pintype "passive"))
      (node (ref "U2") (pin "16") (pinfunction "C_16") (pintype "passive"))
    )
    (net (code "104") (name "Net-(Q5-G)") (class "Default")
      (node (ref "Q5") (pin "1") (pinfunction "G_1") (pintype "passive"))
      (node (ref "R13") (pin "1") (pinfunction "1_1") (pintype "passive"))
      (node (ref "U2") (pin "10") (pinfunction "C_10") (pintype "passive"))
    )
    (net (code "105") (name "Net-(Q6-G)") (class "Default")
      (node (ref "Q6") (pin "1") (pinfunction "G_1") (pintype "passive"))
      (node (ref "R14") (pin "1") (pinfunction "1_1") (pintype "passive"))
      (node (ref "U1") (pin "14") (pinfunction "C_14") (pintype "passive"))
    )
    (net (code "106") (name "Net-(Q7-G)") (class "Default")
      (node (ref "Q7") (pin "1") (pinfunction "G_1") (pintype "passive"))
      (node (ref "R15") (pin "1") (pinfunction "1_1") (pintype "passive"))
      (node (ref "U1") (pin "10") (pinfunction "C_10") (pintype "passive"))
    )
    (net (code "107") (name "Net-(Q8-G)") (class "Default")
      (node (ref "Q8") (pin "1") (pinfunction "G_1") (pintype "passive"))
      (node (ref "R16") (pin "1") (pinfunction "1_1") (pintype "passive"))
      (node (ref "U2") (pin "14") (pinfunction "C_14") (pintype "passive"))
    )
    (net (code "108") (name "Net-(Q9-G)") (class "Default")
      (node (ref "Q9") (pin "1") (pinfunction "G_1") (pintype "passive"))
      (node (ref "R88") (pin "1") (pinfunction "1_1") (pintype "passive"))
      (node (ref "U22") (pin "14") (pinfunction "C_14") (pintype "passive"))
    )
    (net (code "109") (name "Net-(Q10-G)") (class "Default")
      (node (ref "Q10") (pin "1") (pinfunction "G_1") (pintype "passive"))
      (node (ref "R112") (pin "1") (pinfunction "1_1") (pintype "passive"))
      (node (ref "U22") (pin "12") (pinfunction "C_12") (pintype "passive"))
    )
    (net (code "110") (name "Net-(U1A-A)") (class "Default")
      (node (ref "R10") (pin "2") (pinfunction "2_2") (pintype "passive"))
      (node (ref "U1") (pin "1") (pinfunction "A_1") (pintype "passive"))
      (node (ref "U1") (pin "3") (pinfunction "A_3") (pintype "passive"))
    )
    (net (code "111") (name "Net-(U1C-A)") (class "Default")
      (node (ref "R11") (pin "2") (pinfunction "2_2") (pintype "passive"))
      (node (ref "U1") (pin "5") (pinfunction "A_5") (pintype "passive"))
      (node (ref "U1") (pin "7") (pinfunction "A_7") (pintype "passive"))
    )
    (net (code "112") (name "Net-(U2A-A)") (class "Default")
      (node (ref "R12") (pin "2") (pinfunction "2_2") (pintype "passive"))
      (node (ref "U2") (pin "1") (pinfunction "A_1") (pintype "passive"))
      (node (ref "U2") (pin "3") (pinfunction "A_3") (pintype "passive"))
    )
    (net (code "113") (name "Net-(U2C-A)") (class "Default")
      (node (ref "R9") (pin "2") (pinfunction "2_2") (pintype "passive"))
      (node (ref "U2") (pin "5") (pinfunction "A_5") (pintype "passive"))
      (node (ref "U2") (pin "7") (pinfunction "A_7") (pintype "passive"))
    )
    (net (code "114") (name "Net-(U3A-A)") (class "Default")
      (node (ref "R3") (pin "2") (pinfunction "2_2") (pintype "passive"))
      (node (ref "U3") (pin "1") (pinfunction "A_1") (pintype "passive"))
    )
    (net (code "115") (name "Net-(U3A-C)") (class "Default")
      (node (ref "R1") (pin "1") (pinfunction "1_1") (pintype "passive"))
      (node (ref "U3") (pin "16") (pinfunction "C_16") (pintype "passive"))
      (node (ref "U4") (pin "4") (pinfunction "G_4") (pintype "passive"))
    )
    (net (code "116") (name "Net-(U3B-A)") (class "Default")
      (node (ref "R27") (pin "2") (pinfunction "2_2") (pintype "passive"))
      (node (ref "U3") (pin "3") (pinfunction "A_3") (pintype "passive"))
    )
    (net (code "117") (name "Net-(U3B-C)") (class "Default")
      (node (ref "R21") (pin "1") (pinfunction "1_1") (pintype "passive"))
      (node (ref "U3") (pin "14") (pinfunction "C_14") (pintype "passive"))
      (node (ref "U6") (pin "4") (pinfunction "G_4") (pintype "passive"))
    )
    (net (code "118") (name "Net-(U3C-A)") (class "Default")
      (node (ref "R4") (pin "2") (pinfunction "2_2") (pintype "passive"))
      (node (ref "U3") (pin "5") (pinfunction "A_5") (pintype "passive"))
    )
    (net (code "119") (name "Net-(U3C-C)") (class "Default")
      (node (ref "R2") (pin "1") (pinfunction "1_1") (pintype "passive"))
      (node (ref "U3") (pin "12") (pinfunction "C_12") (pintype "passive"))
      (node (ref "U5") (pin "4") (pinfunction "G_4") (pintype "passive"))
    )
    (net (code "120") (name "Net-(U3D-A)") (class "Default")
      (node (ref "R28") (pin "2") (pinfunction "2_2") (pintype "passive"))
      (node (ref "U3") (pin "7") (pinfunction "A_7") (pintype "passive"))
    )
    (net (code "121") (name "Net-(U3D-C)") (class "Default")
      (node (ref "R26") (pin "1") (pinfunction "1_1") (pintype "passive"))
      (node (ref "U3") (pin "10") (pinfunction "C_10") (pintype "passive"))
      (node (ref "U7") (pin "4") (pinfunction "G_4") (pintype "passive"))
    )
    (net (code "122") (name "Net-(U8-1IN+)") (class "Default")
      (node (ref "R37") (pin "2") (pinfunction "2_2") (pintype "passive"))
      (node (ref "R45") (pin "1") (pinfunction "1_1") (pintype "passive"))
      (node (ref "U8") (pin "3") (pinfunction "1IN+_3") (pintype "passive"))
      (node (ref "U8") (pin "5") (pinfunction "2IN+_5") (pintype "passive"))
    )
    (net (code "123") (name "Net-(U9-1IN+)") (class "Default")
      (node (ref "R39") (pin "2") (pinfunction "2_2") (pintype "passive"))
      (node (ref "R46") (pin "1") (pinfunction "1_1") (pintype "passive"))
      (node (ref "U9") (pin "3") (pinfunction "1IN+_3") (pintype "passive"))
      (node (ref "U9") (pin "5") (pinfunction "2IN+_5") (pintype "passive"))
    )
    (net (code "124") (name "Net-(U10-1IN+)") (class "Default")
      (node (ref "R41") (pin "2") (pinfunction "2_2") (pintype "passive"))
      (node (ref "R49") (pin "1") (pinfunction "1_1") (pintype "passive"))
      (node (ref "U10") (pin "3") (pinfunction "1IN+_3") (pintype "passive"))
      (node (ref "U10") (pin "5") (pinfunction "2IN+_5") (pintype "passive"))
    )
    (net (code "125") (name "Net-(U11-1IN+)") (class "Default")
      (node (ref "R43") (pin "2") (pinfunction "2_2") (pintype "passive"))
      (node (ref "R50") (pin "1") (pinfunction "1_1") (pintype "passive"))
      (node (ref "U11") (pin "3") (pinfunction "1IN+_3") (pintype "passive"))
      (node (ref "U11") (pin "5") (pinfunction "2IN+_5") (pintype "passive"))
    )
    (net (code "126") (name "Net-(U12-1IN+)") (class "Default")
      (node (ref "R63") (pin "2") (pinfunction "2_2") (pintype "passive"))
      (node (ref "R69") (pin "1") (pinfunction "1_1") (pintype "passive"))
      (node (ref "U12") (pin "3") (pinfunction "1IN+_3") (pintype "passive"))
      (node (ref "U12") (pin "6") (pinfunction "2IN-_6") (pintype "passive"))
    )
    (net (code "127") (name "Net-(U13-1IN+)") (class "Default")
      (node (ref "R64") (pin "2") (pinfunction "2_2") (pintype "passive"))
      (node (ref "R70") (pin "1") (pinfunction "1_1") (pintype "passive"))
      (node (ref "U13") (pin "3") (pinfunction "1IN+_3") (pintype "passive"))
      (node (ref "U13") (pin "6") (pinfunction "2IN-_6") (pintype "passive"))
    )
    (net (code "128") (name "Net-(U14-1IN+)") (class "Default")
      (node (ref "R67") (pin "2") (pinfunction "2_2") (pintype "passive"))
      (node (ref "R71") (pin "1") (pinfunction "1_1") (pintype "passive"))
      (node (ref "U14") (pin "3") (pinfunction "1IN+_3") (pintype "passive"))
      (node (ref "U14") (pin "6") (pinfunction "2IN-_6") (pintype "passive"))
    )
    (net (code "129") (name "Net-(U15-1IN+)") (class "Default")
      (node (ref "R68") (pin "2") (pinfunction "2_2") (pintype "passive"))
      (node (ref "R72") (pin "1") (pinfunction "1_1") (pintype "passive"))
      (node (ref "U15") (pin "3") (pinfunction "1IN+_3") (pintype "passive"))
      (node (ref "U15") (pin "6") (pinfunction "2IN-_6") (pintype "passive"))
    )
    (net (code "130") (name "Net-(U16A-A)") (class "Default")
      (node (ref "R17") (pin "2") (pinfunction "2_2") (pintype "passive"))
      (node (ref "U16") (pin "1") (pinfunction "A_1") (pintype "passive"))
    )
    (net (code "131") (name "Net-(U16B-A)") (class "Default")
      (node (ref "R22") (pin "2") (pinfunction "2_2") (pintype "passive"))
      (node (ref "U16") (pin "3") (pinfunction "A_3") (pintype "passive"))
    )
    (net (code "132") (name "Net-(U16C-A)") (class "Default")
      (node (ref "R77") (pin "2") (pinfunction "2_2") (pintype "passive"))
      (node (ref "U16") (pin "5") (pinfunction "A_5") (pintype "passive"))
    )
    (net (code "133") (name "Net-(U17-1IN+)") (class "Default")
      (node (ref "R23") (pin "2") (pinfunction "2_2") (pintype "passive"))
      (node (ref "R24") (pin "1") (pinfunction "1_1") (pintype "passive"))
      (node (ref "U17") (pin "3") (pinfunction "1IN+_3") (pintype "passive"))
      (node (ref "U17") (pin "5") (pinfunction "2IN+_5") (pintype "passive"))
    )
    (net (code "134") (name "Net-(U18-1IN+)") (class "Default")
      (node (ref "R81") (pin "2") (pinfunction "2_2") (pintype "passive"))
      (node (ref "R82") (pin "1") (pinfunction "1_1") (pintype "passive"))
      (node (ref "U18") (pin "3") (pinfunction "1IN+_3") (pintype "passive"))
      (node (ref "U18") (pin "6") (pinfunction "2IN-_6") (pintype "passive"))
    )
    (net (code "135") (name "Net-(U19-G)") (class "Default")
      (node (ref "R86") (pin "1") (pinfunction "1_1") (pintype "passive"))
      (node (ref "U19") (pin "4") (pinfunction "G_4") (pintype "passive"))
      (node (ref "U22") (pin "16") (pinfunction "C_16") (pintype "passive"))
    )
    (net (code "136") (name "Net-(U22A-A)") (class "Default")
      (node (ref "R87") (pin "2") (pinfunction "2_2") (pintype "passive"))
      (node (ref "U22") (pin "1") (pinfunction "A_1") (pintype "passive"))
    )
    (net (code "137") (name "Net-(U22B-A)") (class "Default")
      (node (ref "R89") (pin "2") (pinfunction "2_2") (pintype "passive"))
      (node (ref "U22") (pin "3") (pinfunction "A_3") (pintype "passive"))
      (node (ref "U22") (pin "5") (pinfunction "A_5") (pintype "passive"))
    )
    (net (code "138") (name "Net-(U22D-A)") (class "Default")
      (node (ref "R114") (pin "2") (pinfunction "2_2") (pintype "passive"))
      (node (ref "U22") (pin "7") (pinfunction "A_7") (pintype "passive"))
    )
    (net (code "139") (name "Net-(U22D-C)") (class "Default")
      (node (ref "R113") (pin "1") (pinfunction "1_1") (pintype "passive"))
      (node (ref "U22") (pin "10") (pinfunction "C_10") (pintype "passive"))
      (node (ref "U23") (pin "4") (pinfunction "G_4") (pintype "passive"))
    )
    (net (code "140") (name "Net-(U24-LED_DATA-Pad13)") (class "Default")
      (node (ref "U24") (pin "13") (pinfunction "LED_DATA_13") (pintype "passive"))
      (node (ref "U24") (pin "7") (pinfunction "LED_DATA_7") (pintype "passive"))
    )
    (net (code "141") (name "Net-(U24-LED_LINK-Pad12)") (class "Default")
      (node (ref "U24") (pin "12") (pinfunction "LED_LINK_12") (pintype "passive"))
      (node (ref "U24") (pin "16") (pinfunction "LED_LINK_16") (pintype "passive"))
    )
    (net (code "142") (name "Net-(U25-BOOT0)") (class "Default")
      (node (ref "R91") (pin "2") (pinfunction "2_2") (pintype "passive"))
      (node (ref "U25") (pin "60") (pinfunction "BOOT0_60") (pintype "passive"))
    )
    (net (code "143") (name "Net-(U25-NRST)") (class "Default")
      (node (ref "R93") (pin "2") (pinfunction "2_2") (pintype "passive"))
      (node (ref "U25") (pin "7") (pinfunction "NRST_7") (pintype "passive"))
    )
    (net (code "144") (name "Net-(U25-PB2{slash}BOOT1)") (class "Default")
      (node (ref "R94") (pin "2") (pinfunction "2_2") (pintype "passive"))
      (node (ref "U25") (pin "28") (pinfunction "PB2/BOOT1_28") (pintype "passive"))
    )
    (net (code "145") (name "Net-(U25-PD0{slash}OSCIN)") (class "Default")
      (node (ref "C23") (pin "2") (pinfunction "2_2") (pintype "passive"))
      (node (ref "R92") (pin "1") (pinfunction "1_1") (pintype "passive"))
      (node (ref "U25") (pin "5") (pinfunction "PD0/OSCIN_5") (pintype "passive"))
      (node (ref "Y1") (pin "1") (pinfunction "OSC1_1") (pintype "passive"))
    )
    (net (code "146") (name "Net-(U25-PD1{slash}OSCOUT)") (class "Default")
      (node (ref "C24") (pin "2") (pinfunction "2_2") (pintype "passive"))
      (node (ref "R92") (pin "2") (pinfunction "2_2") (pintype "passive"))
      (node (ref "U25") (pin "6") (pinfunction "PD1/OSCOUT_6") (pintype "passive"))
      (node (ref "Y1") (pin "2") (pinfunction "OSC2_2") (pintype "passive"))
    )
    (net (code "147") (name "Net-(U26A-A)") (class "Default")
      (node (ref "R29") (pin "2") (pinfunction "2_2") (pintype "passive"))
      (node (ref "U26") (pin "1") (pinfunction "A_1") (pintype "passive"))
    )
    (net (code "148") (name "Net-(U26B-A)") (class "Default")
      (node (ref "R38") (pin "2") (pinfunction "2_2") (pintype "passive"))
      (node (ref "U26") (pin "3") (pinfunction "A_3") (pintype "passive"))
    )
    (net (code "149") (name "Net-(U26C-A)") (class "Default")
      (node (ref "R53") (pin "2") (pinfunction "2_2") (pintype "passive"))
      (node (ref "U26") (pin "5") (pinfunction "A_5") (pintype "passive"))
    )
    (net (code "150") (name "Net-(U27A-A)") (class "Default")
      (node (ref "R30") (pin "2") (pinfunction "2_2") (pintype "passive"))
      (node (ref "U27") (pin "1") (pinfunction "A_1") (pintype "passive"))
    )
    (net (code "151") (name "Net-(U27B-A)") (class "Default")
      (node (ref "R40") (pin "2") (pinfunction "2_2") (pintype "passive"))
      (node (ref "U27") (pin "3") (pinfunction "A_3") (pintype "passive"))
    )
    (net (code "152") (name "Net-(U27C-A)") (class "Default")
      (node (ref "R54") (pin "2") (pinfunction "2_2") (pintype "passive"))
      (node (ref "U27") (pin "5") (pinfunction "A_5") (pintype "passive"))
    )
    (net (code "153") (name "Net-(U28A-A)") (class "Default")
      (node (ref "R31") (pin "2") (pinfunction "2_2") (pintype "passive"))
      (node (ref "U28") (pin "1") (pinfunction "A_1") (pintype "passive"))
    )
    (net (code "154") (name "Net-(U28B-A)") (class "Default")
      (node (ref "R42") (pin "2") (pinfunction "2_2") (pintype "passive"))
      (node (ref "U28") (pin "3") (pinfunction "A_3") (pintype "passive"))
    )
    (net (code "155") (name "Net-(U28C-A)") (class "Default")
      (node (ref "R55") (pin "2") (pinfunction "2_2") (pintype "passive"))
      (node (ref "U28") (pin "5") (pinfunction "A_5") (pintype "passive"))
    )
    (net (code "156") (name "Net-(U29A-A)") (class "Default")
      (node (ref "R32") (pin "2") (pinfunction "2_2") (pintype "passive"))
      (node (ref "U29") (pin "1") (pinfunction "A_1") (pintype "passive"))
    )
    (net (code "157") (name "Net-(U29B-A)") (class "Default")
      (node (ref "R44") (pin "2") (pinfunction "2_2") (pintype "passive"))
      (node (ref "U29") (pin "3") (pinfunction "A_3") (pintype "passive"))
    )
    (net (code "158") (name "Net-(U29C-A)") (class "Default")
      (node (ref "R56") (pin "2") (pinfunction "2_2") (pintype "passive"))
      (node (ref "U29") (pin "5") (pinfunction "A_5") (pintype "passive"))
    )
    (net (code "159") (name "unconnected-(Pad1-Pad1)") (class "Default")
      (node (ref "Pad1") (pin "1") (pinfunction "1_1") (pintype "passive"))
    )
    (net (code "160") (name "unconnected-(Pad2-Pad1)") (class "Default")
      (node (ref "Pad2") (pin "1") (pinfunction "1_1") (pintype "passive"))
    )
    (net (code "161") (name "unconnected-(Pad3-Pad1)") (class "Default")
      (node (ref "Pad3") (pin "1") (pinfunction "1_1") (pintype "passive"))
    )
    (net (code "162") (name "unconnected-(Pad4-Pad1)") (class "Default")
      (node (ref "Pad4") (pin "1") (pinfunction "1_1") (pintype "passive"))
    )
    (net (code "163") (name "unconnected-(U21-NC-Pad8)") (class "Default")
      (node (ref "U21") (pin "8") (pinfunction "NC_8") (pintype "passive"))
    )
    (net (code "164") (name "unconnected-(U24-CTS-Pad3)") (class "Default")
      (node (ref "U24") (pin "3") (pinfunction "CTS_3") (pintype "passive"))
    )
    (net (code "165") (name "unconnected-(U24-NC-Pad1)") (class "Default")
      (node (ref "U24") (pin "1") (pinfunction "NC_1") (pintype "passive"))
    )
    (net (code "166") (name "unconnected-(U24-NC-Pad2)") (class "Default")
      (node (ref "U24") (pin "2") (pinfunction "NC_2") (pintype "passive"))
    )
    (net (code "167") (name "unconnected-(U24-RTS-Pad5)") (class "Default")
      (node (ref "U24") (pin "5") (pinfunction "RTS_5") (pintype "passive"))
    )
    (net (code "168") (name "unconnected-(U24-Reload-Pad6)") (class "Default")
      (node (ref "U24") (pin "6") (pinfunction "Reload_6") (pintype "passive"))
    )
    (net (code "169") (name "unconnected-(U25-PA0{slash}WKUP{slash}ADC0{slash}TIM2_CH1_ETR{slash}TIM5_CH1{slash}TIM8_ETR-Pad14)") (class "Default")
      (node (ref "U25") (pin "14") (pinfunction "PA0/WKUP/ADC0/TIM2_CH1_ETR/TIM5_CH1/TIM8_ETR_14") (pintype "passive"))
    )
    (net (code "170") (name "unconnected-(U25-PA3{slash}U2_RX{slash}ADC3{slash}TIM2_CH4{slash}TIM5_CH4-Pad17)") (class "Default")
      (node (ref "U25") (pin "17") (pinfunction "PA3/U2_RX/ADC3/TIM2_CH4/TIM5_CH4_17") (pintype "passive"))
    )
    (net (code "171") (name "unconnected-(U25-PA4{slash}SPI1_NSS{slash}ADC4{slash}DAC1-Pad20)") (class "Default")
      (node (ref "U25") (pin "20") (pinfunction "PA4/SPI1_NSS/ADC4/DAC1_20") (pintype "passive"))
    )
    (net (code "172") (name "unconnected-(U25-PA12{slash}CAN_TX{slash}USBDP{slash}TIM1_ETR-Pad45)") (class "Default")
      (node (ref "U25") (pin "45") (pinfunction "PA12/CAN_TX/USBDP/TIM1_ETR_45") (pintype "passive"))
    )
    (net (code "173") (name "unconnected-(U25-PA15{slash}JTDI{slash}SPI3_NSS{slash}I2S3_WS-Pad50)") (class "Default")
      (node (ref "U25") (pin "50") (pinfunction "PA15/JTDI/SPI3_NSS/I2S3_WS_50") (pintype "passive"))
    )
    (net (code "174") (name "unconnected-(U25-PB7{slash}I2C1_SDA{slash}TIM4_CH2-Pad59)") (class "Default")
      (node (ref "U25") (pin "59") (pinfunction "PB7/I2C1_SDA/TIM4_CH2_59") (pintype "passive"))
    )
    (net (code "175") (name "unconnected-(U25-PB8{slash}TIM4_CH3{slash}SDIO_D4-Pad61)") (class "Default")
      (node (ref "U25") (pin "61") (pinfunction "PB8/TIM4_CH3/SDIO_D4_61") (pintype "passive"))
    )
    (net (code "176") (name "unconnected-(U25-PB9{slash}TIM4_CH4{slash}SDIO_D5-Pad62)") (class "Default")
      (node (ref "U25") (pin "62") (pinfunction "PB9/TIM4_CH4/SDIO_D5_62") (pintype "passive"))
    )
    (net (code "177") (name "unconnected-(U25-PC13{slash}ANT1-Pad2)") (class "Default")
      (node (ref "U25") (pin "2") (pinfunction "PC13/ANT1_2") (pintype "passive"))
    )
    (net (code "178") (name "unconnected-(U25-PC14{slash}OSC32-Pad3)") (class "Default")
      (node (ref "U25") (pin "3") (pinfunction "PC14/OSC32_3") (pintype "passive"))
    )
    (net (code "179") (name "unconnected-(U25-PC15{slash}OSC32-Pad4)") (class "Default")
      (node (ref "U25") (pin "4") (pinfunction "PC15/OSC32_4") (pintype "passive"))
    )
    (net (code "180") (name "unconnected-(U25-VBAT-Pad1)") (class "Default")
      (node (ref "U25") (pin "1") (pinfunction "VBAT_1") (pintype "passive"))
    )
  )
)
